# IPMC_MACP_-_1.net
KiCad netlist of a schematic drawn in Altium Designer
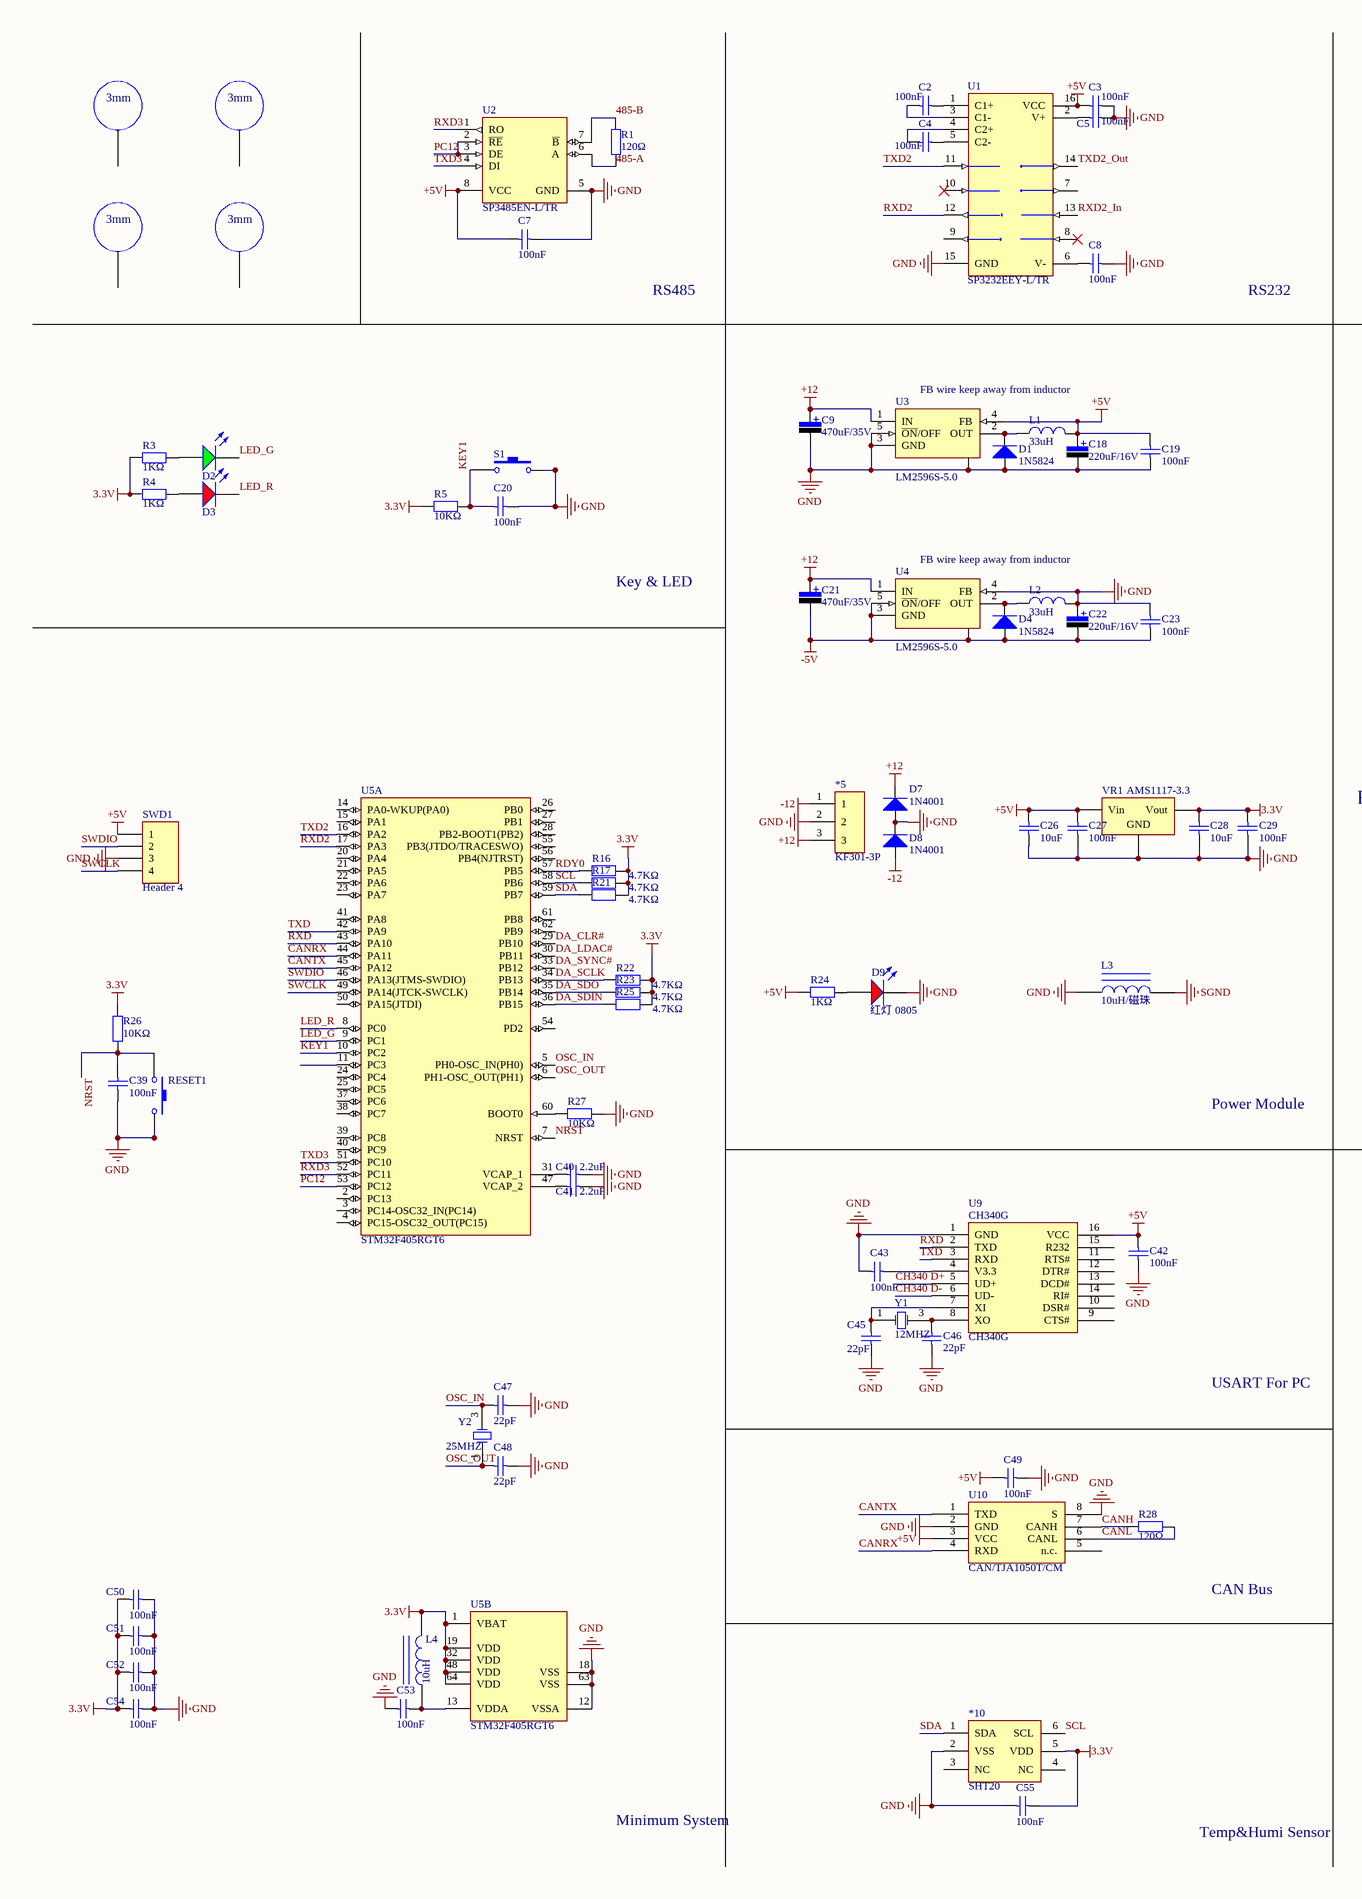
[diagram p0: IPMC_MACP - 完成1.SchDoc, left]
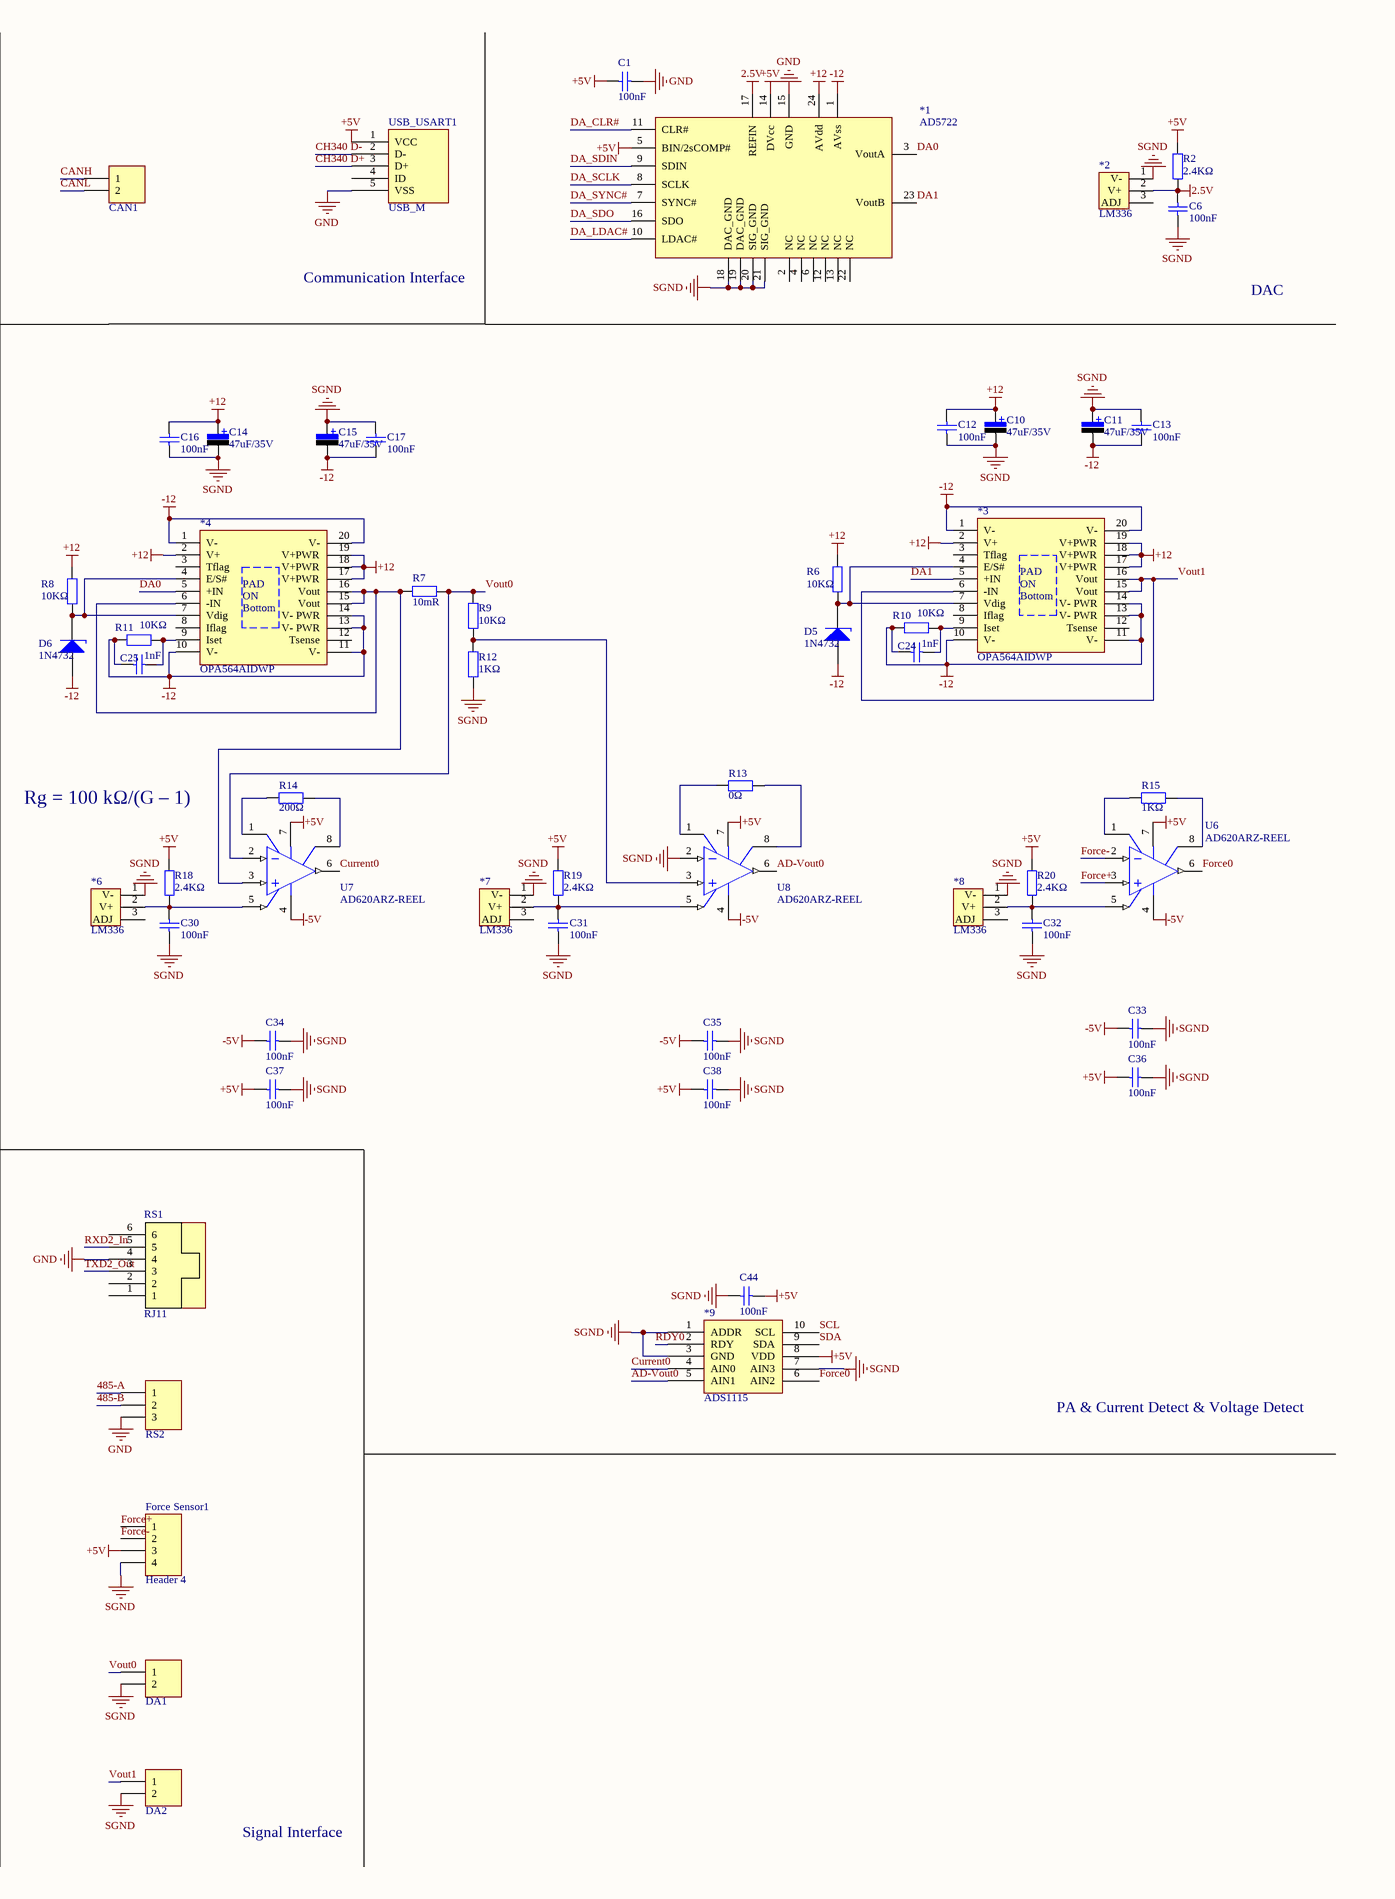
[diagram p1: IPMC_MACP - 完成1.SchDoc, right]

(export (version "E")
  (design (tool "Eeschema 10.0.6"))
  (components
    (comp (ref "*1")
      (value "AD5722")
      (footprint "TSSOP24P")
      (description "双极性DAC")
      (libsource (lib "fszhang") (part "AD5722"))
    )
    (comp (ref "*2")
      (value "LM336")
      (footprint "TO-92A")
      (description "基准电压芯片2.5/5V")
      (libsource (lib "fszhang") (part "LM336"))
    )
    (comp (ref "*3")
      (value "OPA564AIDWP")
      (footprint "HSOP20")
      (description "PAD on Bottom")
      (libsource (lib "fszhang") (part "OPA564AIDWP"))
    )
    (comp (ref "*4")
      (value "OPA564AIDWP")
      (footprint "HSOP20")
      (description "PAD on Bottom")
      (libsource (lib "fszhang") (part "OPA564AIDWP"))
    )
    (comp (ref "*5")
      (value "KF301-3P")
      (footprint "KF301-3P")
      (description "蓝色端子")
      (libsource (lib "fszhang") (part "KF301-3P"))
    )
    (comp (ref "*6")
      (value "LM336")
      (footprint "TO-92A")
      (description "基准电压芯片2.5/5V")
      (libsource (lib "fszhang") (part "LM336"))
    )
    (comp (ref "*7")
      (value "LM336")
      (footprint "TO-92A")
      (description "基准电压芯片2.5/5V")
      (libsource (lib "fszhang") (part "LM336"))
    )
    (comp (ref "*8")
      (value "LM336")
      (footprint "TO-92A")
      (description "基准电压芯片2.5/5V")
      (libsource (lib "fszhang") (part "LM336"))
    )
    (comp (ref "*9") (value "ADS1115") (footprint "MSOP-UN10_N") (libsource (lib "fszhang") (part "ADS1115")))
    (comp (ref "*10") (value "SHT20") (footprint "DFN6") (libsource (lib "fszhang") (part "SHT20")))
    (comp (ref "C1")
      (value "100nF")
      (footprint "0805_C")
      (description "贴片电容")
      (libsource (lib "Miscellaneous Devices LC") (part "0805 100nF(104) 10% 50V"))
    )
    (comp (ref "C2")
      (value "100nF")
      (footprint "0805_C")
      (description "贴片电容")
      (libsource (lib "Miscellaneous Devices LC") (part "0805 100nF(104) 10% 50V"))
    )
    (comp (ref "C3")
      (value "100nF")
      (footprint "0805_C")
      (description "贴片电容")
      (libsource (lib "Miscellaneous Devices LC") (part "0805 100nF(104) 10% 50V"))
    )
    (comp (ref "C4")
      (value "100nF")
      (footprint "0805_C")
      (description "贴片电容")
      (libsource (lib "Miscellaneous Devices LC") (part "0805 100nF(104) 10% 50V"))
    )
    (comp (ref "C5")
      (value "100nF")
      (footprint "0805_C")
      (description "贴片电容")
      (libsource (lib "Miscellaneous Devices LC") (part "0805 100nF(104) 10% 50V"))
    )
    (comp (ref "C6")
      (value "100nF")
      (footprint "0805_C")
      (description "贴片电容")
      (libsource (lib "Miscellaneous Devices LC") (part "0805 100nF(104) 10% 50V"))
    )
    (comp (ref "C7")
      (value "100nF")
      (footprint "0805_C")
      (description "贴片电容")
      (libsource (lib "Miscellaneous Devices LC") (part "0805 100nF(104) 10% 50V"))
    )
    (comp (ref "C8")
      (value "100nF")
      (footprint "0805_C")
      (description "贴片电容")
      (libsource (lib "Miscellaneous Devices LC") (part "0805 100nF(104) 10% 50V"))
    )
    (comp (ref "C9")
      (value "470uF/35V")
      (footprint "C-RB-S10")
      (description "极性电解电容")
      (fields (field (name "PUBLISHER") "Altium Limited"))
      (libsource (lib "fszhang") (part "Cap Pol"))
    )
    (comp (ref "C10")
      (value "47uF/35V")
      (footprint "C-RB-S6")
      (description "极性电解电容")
      (fields (field (name "PUBLISHER") "Altium Limited"))
      (libsource (lib "fszhang") (part "Cap Pol"))
    )
    (comp (ref "C11")
      (value "47uF/35V")
      (footprint "C-RB-S6")
      (description "极性电解电容")
      (fields (field (name "PUBLISHER") "Altium Limited"))
      (libsource (lib "fszhang") (part "Cap Pol"))
    )
    (comp (ref "C12")
      (value "100nF")
      (footprint "0805_C")
      (description "贴片电容")
      (libsource (lib "Miscellaneous Devices LC") (part "0805 100nF(104) 10% 50V"))
    )
    (comp (ref "C13")
      (value "100nF")
      (footprint "0805_C")
      (description "贴片电容")
      (libsource (lib "Miscellaneous Devices LC") (part "0805 100nF(104) 10% 50V"))
    )
    (comp (ref "C14")
      (value "47uF/35V")
      (footprint "C-RB-S6")
      (description "极性电解电容")
      (fields (field (name "PUBLISHER") "Altium Limited"))
      (libsource (lib "fszhang") (part "Cap Pol"))
    )
    (comp (ref "C15")
      (value "47uF/35V")
      (footprint "C-RB-S6")
      (description "极性电解电容")
      (fields (field (name "PUBLISHER") "Altium Limited"))
      (libsource (lib "fszhang") (part "Cap Pol"))
    )
    (comp (ref "C16")
      (value "100nF")
      (footprint "0805_C")
      (description "贴片电容")
      (libsource (lib "Miscellaneous Devices LC") (part "0805 100nF(104) 10% 50V"))
    )
    (comp (ref "C17")
      (value "100nF")
      (footprint "0805_C")
      (description "贴片电容")
      (libsource (lib "Miscellaneous Devices LC") (part "0805 100nF(104) 10% 50V"))
    )
    (comp (ref "C18")
      (value "220uF/16V")
      (footprint "C-RB-S6")
      (description "极性电解电容")
      (fields (field (name "PUBLISHER") "Altium Limited"))
      (libsource (lib "fszhang") (part "Cap Pol"))
    )
    (comp (ref "C19")
      (value "100nF")
      (footprint "0805_C")
      (description "贴片电容")
      (libsource (lib "Miscellaneous Devices LC") (part "0805 100nF(104) 10% 50V"))
    )
    (comp (ref "C20")
      (value "100nF")
      (footprint "0805_C")
      (description "贴片电容")
      (libsource (lib "Miscellaneous Devices LC") (part "0805 100nF(104) 10% 50V"))
    )
    (comp (ref "C21")
      (value "470uF/35V")
      (footprint "C-RB-S10")
      (description "极性电解电容")
      (fields (field (name "PUBLISHER") "Altium Limited"))
      (libsource (lib "fszhang") (part "Cap Pol"))
    )
    (comp (ref "C22")
      (value "220uF/16V")
      (footprint "C-RB-S6")
      (description "极性电解电容")
      (fields (field (name "PUBLISHER") "Altium Limited"))
      (libsource (lib "fszhang") (part "Cap Pol"))
    )
    (comp (ref "C23")
      (value "100nF")
      (footprint "0805_C")
      (description "贴片电容")
      (libsource (lib "Miscellaneous Devices LC") (part "0805 100nF(104) 10% 50V"))
    )
    (comp (ref "C24")
      (value "1nF")
      (footprint "0805_C")
      (description "贴片电容")
      (libsource (lib "Miscellaneous Devices LC") (part "0805 1nF (102) 10% 50V"))
    )
    (comp (ref "C25")
      (value "1nF")
      (footprint "0805_C")
      (description "贴片电容")
      (libsource (lib "Miscellaneous Devices LC") (part "0805 1nF (102) 10% 50V"))
    )
    (comp (ref "C26")
      (value "10uF")
      (footprint "0805_C")
      (description "贴片电容")
      (libsource (lib "Miscellaneous Devices LC") (part "0805 10uF (106) 10% 25V"))
    )
    (comp (ref "C27")
      (value "100nF")
      (footprint "0805_C")
      (description "贴片电容")
      (libsource (lib "Miscellaneous Devices LC") (part "0805 100nF(104) 10% 50V"))
    )
    (comp (ref "C28")
      (value "10uF")
      (footprint "0805_C")
      (description "贴片电容")
      (libsource (lib "Miscellaneous Devices LC") (part "0805 10uF (106) 10% 25V"))
    )
    (comp (ref "C29")
      (value "100nF")
      (footprint "0805_C")
      (description "贴片电容")
      (libsource (lib "Miscellaneous Devices LC") (part "0805 100nF(104) 10% 50V"))
    )
    (comp (ref "C30")
      (value "100nF")
      (footprint "0805_C")
      (description "贴片电容")
      (libsource (lib "Miscellaneous Devices LC") (part "0805 100nF(104) 10% 50V"))
    )
    (comp (ref "C31")
      (value "100nF")
      (footprint "0805_C")
      (description "贴片电容")
      (libsource (lib "Miscellaneous Devices LC") (part "0805 100nF(104) 10% 50V"))
    )
    (comp (ref "C32")
      (value "100nF")
      (footprint "0805_C")
      (description "贴片电容")
      (libsource (lib "Miscellaneous Devices LC") (part "0805 100nF(104) 10% 50V"))
    )
    (comp (ref "C33")
      (value "100nF")
      (footprint "0805_C")
      (description "贴片电容")
      (libsource (lib "Miscellaneous Devices LC") (part "0805 100nF(104) 10% 50V"))
    )
    (comp (ref "C34")
      (value "100nF")
      (footprint "0805_C")
      (description "贴片电容")
      (libsource (lib "Miscellaneous Devices LC") (part "0805 100nF(104) 10% 50V"))
    )
    (comp (ref "C35")
      (value "100nF")
      (footprint "0805_C")
      (description "贴片电容")
      (libsource (lib "Miscellaneous Devices LC") (part "0805 100nF(104) 10% 50V"))
    )
    (comp (ref "C36")
      (value "100nF")
      (footprint "0805_C")
      (description "贴片电容")
      (libsource (lib "Miscellaneous Devices LC") (part "0805 100nF(104) 10% 50V"))
    )
    (comp (ref "C37")
      (value "100nF")
      (footprint "0805_C")
      (description "贴片电容")
      (libsource (lib "Miscellaneous Devices LC") (part "0805 100nF(104) 10% 50V"))
    )
    (comp (ref "C38")
      (value "100nF")
      (footprint "0805_C")
      (description "贴片电容")
      (libsource (lib "Miscellaneous Devices LC") (part "0805 100nF(104) 10% 50V"))
    )
    (comp (ref "C39")
      (value "100nF")
      (footprint "0805_C")
      (description "贴片电容")
      (libsource (lib "Miscellaneous Devices LC") (part "0805 100nF(104) 10% 50V"))
    )
    (comp (ref "C40")
      (value "2.2uF")
      (footprint "0805_C")
      (description "贴片电容")
      (libsource (lib "Miscellaneous Devices LC") (part "0805 2.2uF (225) 20% 50V"))
    )
    (comp (ref "C41")
      (value "2.2uF")
      (footprint "0805_C")
      (description "贴片电容")
      (libsource (lib "Miscellaneous Devices LC") (part "0805 2.2uF (225) 20% 50V"))
    )
    (comp (ref "C42")
      (value "100nF")
      (footprint "0805_C")
      (description "贴片电容")
      (libsource (lib "Miscellaneous Devices LC") (part "0805 100nF(104) 10% 50V"))
    )
    (comp (ref "C43")
      (value "100nF")
      (footprint "0805_C")
      (description "贴片电容")
      (libsource (lib "Miscellaneous Devices LC") (part "0805 100nF(104) 10% 50V"))
    )
    (comp (ref "C44")
      (value "100nF")
      (footprint "0805_C")
      (description "贴片电容")
      (libsource (lib "Miscellaneous Devices LC") (part "0805 100nF(104) 10% 50V"))
    )
    (comp (ref "C45")
      (value "22pF")
      (footprint "0805_C")
      (description "贴片电容")
      (libsource (lib "Miscellaneous Devices LC") (part "0805 22pF (220) 5% 50V"))
    )
    (comp (ref "C46")
      (value "22pF")
      (footprint "0805_C")
      (description "贴片电容")
      (libsource (lib "Miscellaneous Devices LC") (part "0805 22pF (220) 5% 50V"))
    )
    (comp (ref "C47")
      (value "22pF")
      (footprint "0805_C")
      (description "贴片电容")
      (libsource (lib "Miscellaneous Devices LC") (part "0805 22pF (220) 5% 50V"))
    )
    (comp (ref "C48")
      (value "22pF")
      (footprint "0805_C")
      (description "贴片电容")
      (libsource (lib "Miscellaneous Devices LC") (part "0805 22pF (220) 5% 50V"))
    )
    (comp (ref "C49")
      (value "100nF")
      (footprint "0805_C")
      (description "贴片电容")
      (libsource (lib "Miscellaneous Devices LC") (part "0805 100nF(104) 10% 50V"))
    )
    (comp (ref "C50")
      (value "100nF")
      (footprint "0805_C")
      (description "贴片电容")
      (libsource (lib "Miscellaneous Devices LC") (part "0805 100nF(104) 10% 50V"))
    )
    (comp (ref "C51")
      (value "100nF")
      (footprint "0805_C")
      (description "贴片电容")
      (libsource (lib "Miscellaneous Devices LC") (part "0805 100nF(104) 10% 50V"))
    )
    (comp (ref "C52")
      (value "100nF")
      (footprint "0805_C")
      (description "贴片电容")
      (libsource (lib "Miscellaneous Devices LC") (part "0805 100nF(104) 10% 50V"))
    )
    (comp (ref "C53")
      (value "100nF")
      (footprint "0805_C")
      (description "贴片电容")
      (libsource (lib "Miscellaneous Devices LC") (part "0805 100nF(104) 10% 50V"))
    )
    (comp (ref "C54")
      (value "100nF")
      (footprint "0805_C")
      (description "贴片电容")
      (libsource (lib "Miscellaneous Devices LC") (part "0805 100nF(104) 10% 50V"))
    )
    (comp (ref "C55")
      (value "100nF")
      (footprint "0805_C")
      (description "贴片电容")
      (libsource (lib "Miscellaneous Devices LC") (part "0805 100nF(104) 10% 50V"))
    )
    (comp (ref "CAN1")
      (value "Header 2")
      (footprint "HDR2X1_B1")
      (description "接插件")
      (fields (field (name "PUBLISHER") "Altium Limited"))
      (libsource (lib "fszhang") (part "Header 2"))
    )
    (comp (ref "D1")
      (value "1N5824")
      (footprint "DIODE-SMA")
      (description "二极管")
      (fields (field (name "PUBLISHER") "Altium Limited"))
      (libsource (lib "fszhang") (part "Diode"))
    )
    (comp (ref "D2")
      (value "翠绿 0805")
      (footprint "0805_LED_S1")
      (description "发光二极管")
      (libsource (lib "Miscellaneous Devices LC") (part "0805 翠绿"))
    )
    (comp (ref "D3")
      (value "红灯 0805")
      (footprint "0805_LED_S1")
      (description "发光二极管")
      (libsource (lib "Miscellaneous Devices LC") (part "0805 红灯"))
    )
    (comp (ref "D4")
      (value "1N5824")
      (footprint "DIODE-SMA")
      (description "二极管")
      (fields (field (name "PUBLISHER") "Altium Limited"))
      (libsource (lib "fszhang") (part "Diode"))
    )
    (comp (ref "D5")
      (value "1N4732")
      (footprint "DIODE-1206")
      (description "稳压二极管")
      (fields (field (name "PUBLISHER") "Altium Limited"))
      (libsource (lib "fszhang") (part "Diode-Z"))
    )
    (comp (ref "D6")
      (value "1N4732")
      (footprint "DIODE-1206")
      (description "稳压二极管")
      (fields (field (name "PUBLISHER") "Altium Limited"))
      (libsource (lib "fszhang") (part "Diode-Z"))
    )
    (comp (ref "D7")
      (value "1N4001")
      (footprint "DIODE-SMA")
      (description "二极管")
      (fields (field (name "PUBLISHER") "Altium Limited"))
      (libsource (lib "fszhang") (part "Diode"))
    )
    (comp (ref "D8")
      (value "1N4001")
      (footprint "DIODE-SMA")
      (description "二极管")
      (fields (field (name "PUBLISHER") "Altium Limited"))
      (libsource (lib "fszhang") (part "Diode"))
    )
    (comp (ref "D9")
      (value "红灯 0805")
      (footprint "0805_LED_S1")
      (description "发光二极管")
      (libsource (lib "Miscellaneous Devices LC") (part "0805 红灯"))
    )
    (comp (ref "DA1")
      (value "Header 2")
      (footprint "HDR2X1_B1")
      (description "接插件")
      (fields (field (name "PUBLISHER") "Altium Limited"))
      (libsource (lib "fszhang") (part "Header 2"))
    )
    (comp (ref "DA2")
      (value "Header 2")
      (footprint "HDR2X1_B1")
      (description "接插件")
      (fields (field (name "PUBLISHER") "Altium Limited"))
      (libsource (lib "fszhang") (part "Header 2"))
    )
    (comp (ref "Force Sensor1")
      (value "Header 4")
      (footprint "fszhang:HDR4X1_B1")
      (description "Header, 4-Pin")
      (fields (field (name "PUBLISHER") "Altium Limited"))
      (libsource (lib "Miscellaneous Connectors") (part "Header 4"))
    )
    (comp (ref "L1")
      (value "33uH")
      (footprint "L-SMD-12")
      (description "电感")
      (fields (field (name "PUBLISHER") "Altium Limited"))
      (libsource (lib "fszhang") (part "Inductor"))
    )
    (comp (ref "L2")
      (value "33uH")
      (footprint "L-SMD-12")
      (description "电感")
      (fields (field (name "PUBLISHER") "Altium Limited"))
      (libsource (lib "fszhang") (part "Inductor"))
    )
    (comp (ref "L3")
      (value "10uH/磁珠")
      (footprint "0805_L")
      (description "贴片电感")
      (libsource (lib "Miscellaneous Devices LC") (part "0805 10uH 10%"))
    )
    (comp (ref "L4")
      (value "10uH")
      (footprint "0805_L")
      (description "贴片电感")
      (libsource (lib "Miscellaneous Devices LC") (part "0805 10uH 10%"))
    )
    (comp (ref "R1")
      (value "120Ω")
      (footprint "0805_R")
      (description "贴片电阻")
      (libsource (lib "Miscellaneous Devices LC") (part "0805 120Ω (1200) 1%"))
    )
    (comp (ref "R2")
      (value "2.4KΩ")
      (footprint "0805_R")
      (description "贴片电阻")
      (libsource (lib "Miscellaneous Devices LC") (part "0805 2.4KΩ (2401) 1%"))
    )
    (comp (ref "R3")
      (value "1KΩ")
      (footprint "0805_R")
      (description "贴片电阻")
      (libsource (lib "Miscellaneous Devices LC") (part "0805 1KΩ (1001) 1%"))
    )
    (comp (ref "R4")
      (value "1KΩ")
      (footprint "0805_R")
      (description "贴片电阻")
      (libsource (lib "Miscellaneous Devices LC") (part "0805 1KΩ (1001) 1%"))
    )
    (comp (ref "R5")
      (value "10KΩ")
      (footprint "0805_R")
      (description "贴片电阻")
      (libsource (lib "") (part "0805 10KΩ (1002) 1%_2"))
    )
    (comp (ref "R6")
      (value "10KΩ")
      (footprint "0805_R")
      (description "贴片电阻")
      (libsource (lib "") (part "0805 10KΩ (1002) 1%_3"))
    )
    (comp (ref "R7")
      (value "10mR")
      (footprint "2512")
      (description "贴片电阻")
      (fields (field (name "PUBLISHER") "Altium Limited"))
      (libsource (lib "fszhang") (part "Res1"))
    )
    (comp (ref "R8")
      (value "10KΩ")
      (footprint "0805_R")
      (description "贴片电阻")
      (libsource (lib "") (part "0805 10KΩ (1002) 1%_3"))
    )
    (comp (ref "R9")
      (value "10KΩ")
      (footprint "0805_R")
      (description "贴片电阻")
      (libsource (lib "Miscellaneous Devices LC") (part "0805 20KΩ (2002) 1%"))
    )
    (comp (ref "R10")
      (value "10KΩ")
      (footprint "0805_R")
      (description "贴片电阻")
      (libsource (lib "") (part "0805 10KΩ (1002) 1%_2"))
    )
    (comp (ref "R11")
      (value "10KΩ")
      (footprint "0805_R")
      (description "贴片电阻")
      (libsource (lib "") (part "0805 10KΩ (1002) 1%_2"))
    )
    (comp (ref "R12")
      (value "1KΩ")
      (footprint "0805_R")
      (description "贴片电阻")
      (libsource (lib "Miscellaneous Devices LC") (part "0805 20KΩ (2002) 1%"))
    )
    (comp (ref "R13")
      (value "0Ω")
      (footprint "0805_R")
      (description "贴片电阻")
      (libsource (lib "Miscellaneous Devices LC") (part "0805 0Ω (0R0) 1%"))
    )
    (comp (ref "R14")
      (value "200Ω")
      (footprint "0805_R")
      (description "贴片电阻")
      (libsource (lib "Miscellaneous Devices LC") (part "0805 200Ω (2000) 1%"))
    )
    (comp (ref "R15")
      (value "1KΩ")
      (footprint "0805_R")
      (description "贴片电阻")
      (libsource (lib "Miscellaneous Devices LC") (part "0805 1KΩ (1001) 1%"))
    )
    (comp (ref "R16")
      (value "4.7KΩ")
      (footprint "0805_R")
      (description "贴片电阻")
      (libsource (lib "Miscellaneous Devices LC") (part "0805 4.7KΩ (4701) 1%"))
    )
    (comp (ref "R17")
      (value "4.7KΩ")
      (footprint "0805_R")
      (description "贴片电阻")
      (libsource (lib "Miscellaneous Devices LC") (part "0805 4.7KΩ (4701) 1%"))
    )
    (comp (ref "R18")
      (value "2.4KΩ")
      (footprint "0805_R")
      (description "贴片电阻")
      (libsource (lib "Miscellaneous Devices LC") (part "0805 2.4KΩ (2401) 1%"))
    )
    (comp (ref "R19")
      (value "2.4KΩ")
      (footprint "0805_R")
      (description "贴片电阻")
      (libsource (lib "Miscellaneous Devices LC") (part "0805 2.4KΩ (2401) 1%"))
    )
    (comp (ref "R20")
      (value "2.4KΩ")
      (footprint "0805_R")
      (description "贴片电阻")
      (libsource (lib "Miscellaneous Devices LC") (part "0805 2.4KΩ (2401) 1%"))
    )
    (comp (ref "R21")
      (value "4.7KΩ")
      (footprint "0805_R")
      (description "贴片电阻")
      (libsource (lib "Miscellaneous Devices LC") (part "0805 4.7KΩ (4701) 1%"))
    )
    (comp (ref "R22")
      (value "4.7KΩ")
      (footprint "0805_R")
      (description "贴片电阻")
      (libsource (lib "Miscellaneous Devices LC") (part "0805 4.7KΩ (4701) 1%"))
    )
    (comp (ref "R23")
      (value "4.7KΩ")
      (footprint "0805_R")
      (description "贴片电阻")
      (libsource (lib "Miscellaneous Devices LC") (part "0805 4.7KΩ (4701) 1%"))
    )
    (comp (ref "R24")
      (value "1KΩ")
      (footprint "0805_R")
      (description "贴片电阻")
      (libsource (lib "Miscellaneous Devices LC") (part "0805 1KΩ (1001) 1%"))
    )
    (comp (ref "R25")
      (value "4.7KΩ")
      (footprint "0805_R")
      (description "贴片电阻")
      (libsource (lib "Miscellaneous Devices LC") (part "0805 4.7KΩ (4701) 1%"))
    )
    (comp (ref "R26")
      (value "10KΩ")
      (footprint "0805_R")
      (description "贴片电阻")
      (libsource (lib "Miscellaneous Devices LC") (part "0805 10KΩ (1002) 1%"))
    )
    (comp (ref "R27")
      (value "10KΩ")
      (footprint "0805_R")
      (description "贴片电阻")
      (libsource (lib "") (part "0805 10KΩ (1002) 1%_1"))
    )
    (comp (ref "R28")
      (value "120Ω")
      (footprint "0805_R")
      (description "贴片电阻")
      (libsource (lib "") (part "0805 120Ω (1200) 1%_1"))
    )
    (comp (ref "RESET1")
      (value "SW-PB")
      (footprint "SW_PB2_A1")
      (description "微动开关")
      (fields (field (name "PUBLISHER") "Altium Limited"))
      (libsource (lib "fszhang") (part "SW-PB"))
    )
    (comp (ref "RS1") (value "RJ11") (footprint "RJ6-RJ11") (libsource (lib "fszhang") (part "RJ11")))
    (comp (ref "RS2")
      (value "Header 3")
      (footprint "HDR3X1_B1")
      (description "接插件")
      (fields (field (name "PUBLISHER") "Altium Limited"))
      (libsource (lib "fszhang") (part "Header 3"))
    )
    (comp (ref "S1")
      (value "SW-PB")
      (footprint "SW_PB2_A1")
      (description "微动开关")
      (fields (field (name "PUBLISHER") "Altium Limited"))
      (libsource (lib "fszhang") (part "SW-PB"))
    )
    (comp (ref "SWD1")
      (value "Header 4")
      (footprint "HDR1X4")
      (description "Header, 4-Pin")
      (fields (field (name "PUBLISHER") "Altium Limited"))
      (libsource (lib "Miscellaneous Connectors") (part "Header 4"))
    )
    (comp (ref "T1") (value "M3铜柱螺丝孔") (footprint "螺丝孔-3mm") (libsource (lib "fszhang") (part "M3铜柱螺丝孔")))
    (comp (ref "T2") (value "M3铜柱螺丝孔") (footprint "螺丝孔-3mm") (libsource (lib "fszhang") (part "M3铜柱螺丝孔")))
    (comp (ref "T3") (value "M3铜柱螺丝孔") (footprint "螺丝孔-3mm") (libsource (lib "fszhang") (part "M3铜柱螺丝孔")))
    (comp (ref "T4") (value "M3铜柱螺丝孔") (footprint "螺丝孔-3mm") (libsource (lib "fszhang") (part "M3铜柱螺丝孔")))
    (comp (ref "U1")
      (value "SP3232EEY-L/TR")
      (footprint "TSSOP-16")
      (description "RS232")
      (libsource (lib "Miscellaneous Devices LC") (part "SP3232EEY-L/TR"))
    )
    (comp (ref "U2")
      (value "SP3485EN-L/TR")
      (footprint "SOIC-8_150mil")
      (description "RS-485/RS-422")
      (libsource (lib "Miscellaneous Devices LC") (part "SP3485EN-L/TR"))
    )
    (comp (ref "U3")
      (value "LM2596S-5.0")
      (footprint "TO-263-5")
      (description "5V稳压芯片")
      (fields (field (name "PUBLISHER") "Altium Limited"))
      (libsource (lib "fszhang") (part "LM2596S-5.0"))
    )
    (comp (ref "U4")
      (value "LM2596S-5.0")
      (footprint "TO-263-5")
      (description "5V稳压芯片")
      (fields (field (name "PUBLISHER") "Altium Limited"))
      (libsource (lib "fszhang") (part "LM2596S-5.0"))
    )
    (comp (ref "U5")
      (value "STM32F405RGT6")
      (footprint "STM-LQFP64_L")
      (fields (field (name "MANUFACTURER") "STMicroelectronics"))
      (libsource (lib "STMicroelectronics STM32 F4") (part "STM32F405RGT6"))
    )
    (comp (ref "U6")
      (value "AD620ARZ-REEL")
      (footprint "SOIC-8_150mil")
      (description "仪放")
      (libsource (lib "Miscellaneous Devices LC") (part "AD620ARZ-REEL"))
    )
    (comp (ref "U7")
      (value "AD620ARZ-REEL")
      (footprint "SOIC-8_150mil")
      (description "仪放")
      (libsource (lib "Miscellaneous Devices LC") (part "AD620ARZ-REEL"))
    )
    (comp (ref "U8")
      (value "AD620ARZ-REEL")
      (footprint "SOIC-8_150mil")
      (description "仪放")
      (libsource (lib "Miscellaneous Devices LC") (part "AD620ARZ-REEL"))
    )
    (comp (ref "U9")
      (value "CH340G")
      (footprint "SOIC-16_150mil")
      (description "USB")
      (libsource (lib "Miscellaneous Devices LC") (part "CH340G"))
    )
    (comp (ref "U10")
      (value "CAN/TJA1050T/CM")
      (footprint "SOIC-8_150mil")
      (description "CAN")
      (libsource (lib "Miscellaneous Devices LC") (part "CAN/TJA1050T/CM"))
    )
    (comp (ref "USB_USART1")
      (value "USB_M")
      (footprint "USB_MICRO")
      (description "MicroUSB接口")
      (libsource (lib "fszhang") (part "USB_M"))
    )
    (comp (ref "VR1")
      (value "AMS1117-3.3")
      (footprint "SOT-223")
      (description "低压差线性稳压(LDO)")
      (libsource (lib "Miscellaneous Devices LC") (part "SOT-223 AMS1117-3.3"))
    )
    (comp (ref "Y1")
      (value "12MHZ")
      (footprint "SMD-3225_4P")
      (description "贴片晶振")
      (libsource (lib "Miscellaneous Devices LC") (part "SMD-3225_4P  12MHZ 20PF 10PPM"))
    )
    (comp (ref "Y2")
      (value "25MHZ")
      (footprint "SMD-3225_4P")
      (description "贴片晶振")
      (libsource (lib "Miscellaneous Devices LC") (part "SMD-3225_4P  25MHZ 12PF 10PPM"))
    )
  )
  (nets
    (net (code "1") (name "+5V") (class "Default")
      (node (ref "*1") (pin "14") (pinfunction "DVcc_14") (pintype "passive"))
      (node (ref "*1") (pin "5") (pinfunction "BIN/2sCOMP#_5") (pintype "passive"))
      (node (ref "*9") (pin "8") (pinfunction "VDD_8") (pintype "passive"))
      (node (ref "C1") (pin "2") (pinfunction "2_2") (pintype "passive"))
      (node (ref "C18") (pin "1") (pinfunction "1_1") (pintype "passive"))
      (node (ref "C19") (pin "2") (pinfunction "2_2") (pintype "passive"))
      (node (ref "C26") (pin "2") (pinfunction "2_2") (pintype "passive"))
      (node (ref "C27") (pin "2") (pinfunction "2_2") (pintype "passive"))
      (node (ref "C3") (pin "1") (pinfunction "1_1") (pintype "passive"))
      (node (ref "C36") (pin "2") (pinfunction "2_2") (pintype "passive"))
      (node (ref "C37") (pin "2") (pinfunction "2_2") (pintype "passive"))
      (node (ref "C38") (pin "2") (pinfunction "2_2") (pintype "passive"))
      (node (ref "C42") (pin "2") (pinfunction "2_2") (pintype "passive"))
      (node (ref "C44") (pin "1") (pinfunction "1_1") (pintype "passive"))
      (node (ref "C49") (pin "2") (pinfunction "2_2") (pintype "passive"))
      (node (ref "C7") (pin "2") (pinfunction "2_2") (pintype "passive"))
      (node (ref "Force Sensor1") (pin "3") (pinfunction "3_3") (pintype "passive"))
      (node (ref "L1") (pin "2") (pinfunction "2_2") (pintype "passive"))
      (node (ref "R18") (pin "2") (pinfunction "2_2") (pintype "passive"))
      (node (ref "R19") (pin "2") (pinfunction "2_2") (pintype "passive"))
      (node (ref "R2") (pin "2") (pinfunction "2_2") (pintype "passive"))
      (node (ref "R20") (pin "2") (pinfunction "2_2") (pintype "passive"))
      (node (ref "R24") (pin "1") (pinfunction "1_1") (pintype "passive"))
      (node (ref "SWD1") (pin "1") (pinfunction "1_1") (pintype "passive"))
      (node (ref "U1") (pin "16") (pinfunction "VCC_16") (pintype "power_in"))
      (node (ref "U10") (pin "3") (pinfunction "VCC_3") (pintype "passive"))
      (node (ref "U2") (pin "8") (pinfunction "VCC_8") (pintype "power_in"))
      (node (ref "U3") (pin "4") (pinfunction "FB_4") (pintype "input"))
      (node (ref "U6") (pin "7") (pinfunction "V+_7") (pintype "power_in"))
      (node (ref "U7") (pin "7") (pinfunction "V+_7") (pintype "power_in"))
      (node (ref "U8") (pin "7") (pinfunction "V+_7") (pintype "power_in"))
      (node (ref "U9") (pin "16") (pinfunction "VCC_16") (pintype "passive"))
      (node (ref "USB_USART1") (pin "1") (pinfunction "VCC_1") (pintype "passive"))
      (node (ref "VR1") (pin "3") (pinfunction "Vin_3") (pintype "passive"))
    )
    (net (code "2") (name "+12") (class "Default")
      (node (ref "*1") (pin "24") (pinfunction "AVdd_24") (pintype "passive"))
      (node (ref "*3") (pin "17") (pinfunction "V+PWR_17") (pintype "passive"))
      (node (ref "*3") (pin "18") (pinfunction "V+PWR_18") (pintype "passive"))
      (node (ref "*3") (pin "19") (pinfunction "V+PWR_19") (pintype "passive"))
      (node (ref "*3") (pin "2") (pinfunction "V+_2") (pintype "passive"))
      (node (ref "*4") (pin "17") (pinfunction "V+PWR_17") (pintype "passive"))
      (node (ref "*4") (pin "18") (pinfunction "V+PWR_18") (pintype "passive"))
      (node (ref "*4") (pin "19") (pinfunction "V+PWR_19") (pintype "passive"))
      (node (ref "*4") (pin "2") (pinfunction "V+_2") (pintype "passive"))
      (node (ref "*5") (pin "3") (pinfunction "3_3") (pintype "passive"))
      (node (ref "C10") (pin "1") (pinfunction "1_1") (pintype "passive"))
      (node (ref "C12") (pin "2") (pinfunction "2_2") (pintype "passive"))
      (node (ref "C14") (pin "1") (pinfunction "1_1") (pintype "passive"))
      (node (ref "C16") (pin "2") (pinfunction "2_2") (pintype "passive"))
      (node (ref "C21") (pin "1") (pinfunction "1_1") (pintype "passive"))
      (node (ref "C9") (pin "1") (pinfunction "1_1") (pintype "passive"))
      (node (ref "D7") (pin "2") (pinfunction "K_2") (pintype "passive"))
      (node (ref "R6") (pin "2") (pinfunction "2_2") (pintype "passive"))
      (node (ref "R8") (pin "2") (pinfunction "2_2") (pintype "passive"))
      (node (ref "U3") (pin "1") (pinfunction "IN_1") (pintype "power_in"))
      (node (ref "U4") (pin "1") (pinfunction "IN_1") (pintype "power_in"))
    )
    (net (code "3") (name "-5V") (class "Default")
      (node (ref "C21") (pin "2") (pinfunction "2_2") (pintype "passive"))
      (node (ref "C22") (pin "2") (pinfunction "2_2") (pintype "passive"))
      (node (ref "C23") (pin "1") (pinfunction "1_1") (pintype "passive"))
      (node (ref "C33") (pin "2") (pinfunction "2_2") (pintype "passive"))
      (node (ref "C34") (pin "2") (pinfunction "2_2") (pintype "passive"))
      (node (ref "C35") (pin "2") (pinfunction "2_2") (pintype "passive"))
      (node (ref "D4") (pin "1") (pinfunction "A_1") (pintype "passive"))
      (node (ref "U4") (pin "3") (pinfunction "GND_3") (pintype "power_in"))
      (node (ref "U4") (pin "5") (pinfunction "~{ON}/OFF_5") (pintype "input"))
      (node (ref "U4") (pin "6") (pinfunction "6_6") (pintype "power_in"))
      (node (ref "U6") (pin "4") (pinfunction "V-_4") (pintype "power_in"))
      (node (ref "U7") (pin "4") (pinfunction "V-_4") (pintype "power_in"))
      (node (ref "U8") (pin "4") (pinfunction "V-_4") (pintype "power_in"))
    )
    (net (code "4") (name "-12") (class "Default")
      (node (ref "*1") (pin "1") (pinfunction "AVss_1") (pintype "passive"))
      (node (ref "*3") (pin "1") (pinfunction "V-_1") (pintype "passive"))
      (node (ref "*3") (pin "10") (pinfunction "V-_10") (pintype "passive"))
      (node (ref "*3") (pin "11") (pinfunction "V-_11") (pintype "passive"))
      (node (ref "*3") (pin "13") (pinfunction "V-_PWR_13") (pintype "passive"))
      (node (ref "*3") (pin "14") (pinfunction "V-_PWR_14") (pintype "passive"))
      (node (ref "*3") (pin "20") (pinfunction "V-_20") (pintype "passive"))
      (node (ref "*4") (pin "1") (pinfunction "V-_1") (pintype "passive"))
      (node (ref "*4") (pin "10") (pinfunction "V-_10") (pintype "passive"))
      (node (ref "*4") (pin "11") (pinfunction "V-_11") (pintype "passive"))
      (node (ref "*4") (pin "13") (pinfunction "V-_PWR_13") (pintype "passive"))
      (node (ref "*4") (pin "14") (pinfunction "V-_PWR_14") (pintype "passive"))
      (node (ref "*4") (pin "20") (pinfunction "V-_20") (pintype "passive"))
      (node (ref "*5") (pin "1") (pinfunction "1_1") (pintype "passive"))
      (node (ref "C11") (pin "2") (pinfunction "2_2") (pintype "passive"))
      (node (ref "C13") (pin "2") (pinfunction "2_2") (pintype "passive"))
      (node (ref "C15") (pin "2") (pinfunction "2_2") (pintype "passive"))
      (node (ref "C17") (pin "2") (pinfunction "2_2") (pintype "passive"))
      (node (ref "C24") (pin "1") (pinfunction "1_1") (pintype "passive"))
      (node (ref "C25") (pin "1") (pinfunction "1_1") (pintype "passive"))
      (node (ref "D5") (pin "1") (pinfunction "A_1") (pintype "passive"))
      (node (ref "D6") (pin "1") (pinfunction "A_1") (pintype "passive"))
      (node (ref "D8") (pin "1") (pinfunction "A_1") (pintype "passive"))
      (node (ref "R10") (pin "1") (pinfunction "1_1") (pintype "passive"))
      (node (ref "R11") (pin "1") (pinfunction "1_1") (pintype "passive"))
    )
    (net (code "5") (name "/485-A") (class "Default")
      (node (ref "R1") (pin "1") (pinfunction "1_1") (pintype "passive"))
      (node (ref "RS2") (pin "1") (pinfunction "1_1") (pintype "passive"))
      (node (ref "U2") (pin "6") (pinfunction "A_6") (pintype "bidirectional"))
    )
    (net (code "6") (name "/485-B") (class "Default")
      (node (ref "R1") (pin "2") (pinfunction "2_2") (pintype "passive"))
      (node (ref "RS2") (pin "2") (pinfunction "2_2") (pintype "passive"))
      (node (ref "U2") (pin "7") (pinfunction "~{B}_7") (pintype "bidirectional"))
    )
    (net (code "7") (name "/AD-Vout0") (class "Default")
      (node (ref "*9") (pin "5") (pinfunction "AIN1_5") (pintype "passive"))
      (node (ref "U8") (pin "6") (pinfunction "OUT_6") (pintype "output"))
    )
    (net (code "8") (name "/CANH") (class "Default")
      (node (ref "CAN1") (pin "1") (pinfunction "1_1") (pintype "passive"))
      (node (ref "R28") (pin "1") (pinfunction "1_1") (pintype "passive"))
      (node (ref "U10") (pin "7") (pinfunction "CANH_7") (pintype "passive"))
    )
    (net (code "9") (name "/CANL") (class "Default")
      (node (ref "CAN1") (pin "2") (pinfunction "2_2") (pintype "passive"))
      (node (ref "R28") (pin "2") (pinfunction "2_2") (pintype "passive"))
      (node (ref "U10") (pin "6") (pinfunction "CANL_6") (pintype "passive"))
    )
    (net (code "10") (name "/CANRX") (class "Default")
      (node (ref "U10") (pin "4") (pinfunction "RXD_4") (pintype "passive"))
      (node (ref "U5") (pin "44") (pinfunction "PA11_44") (pintype "bidirectional"))
    )
    (net (code "11") (name "/CANTX") (class "Default")
      (node (ref "U10") (pin "1") (pinfunction "TXD_1") (pintype "passive"))
      (node (ref "U5") (pin "45") (pinfunction "PA12_45") (pintype "bidirectional"))
    )
    (net (code "12") (name "/CH340 D+") (class "Default")
      (node (ref "U9") (pin "5") (pinfunction "UD+_5") (pintype "passive"))
      (node (ref "USB_USART1") (pin "3") (pinfunction "D+_3") (pintype "passive"))
    )
    (net (code "13") (name "/CH340 D-") (class "Default")
      (node (ref "U9") (pin "6") (pinfunction "UD-_6") (pintype "passive"))
      (node (ref "USB_USART1") (pin "2") (pinfunction "D-_2") (pintype "passive"))
    )
    (net (code "14") (name "/Current0") (class "Default")
      (node (ref "*9") (pin "4") (pinfunction "AIN0_4") (pintype "passive"))
      (node (ref "U7") (pin "6") (pinfunction "OUT_6") (pintype "output"))
    )
    (net (code "15") (name "/DA0") (class "Default")
      (node (ref "*1") (pin "3") (pinfunction "VoutA_3") (pintype "passive"))
      (node (ref "*4") (pin "5") (pinfunction "+IN_5") (pintype "passive"))
    )
    (net (code "16") (name "/DA1") (class "Default")
      (node (ref "*1") (pin "23") (pinfunction "VoutB_23") (pintype "passive"))
      (node (ref "*3") (pin "5") (pinfunction "+IN_5") (pintype "passive"))
    )
    (net (code "17") (name "/DA_CLR#") (class "Default")
      (node (ref "*1") (pin "11") (pinfunction "CLR#_11") (pintype "passive"))
      (node (ref "U5") (pin "29") (pinfunction "PB10_29") (pintype "bidirectional"))
    )
    (net (code "18") (name "/DA_LDAC#") (class "Default")
      (node (ref "*1") (pin "10") (pinfunction "LDAC#_10") (pintype "passive"))
      (node (ref "U5") (pin "30") (pinfunction "PB11_30") (pintype "bidirectional"))
    )
    (net (code "19") (name "/DA_SCLK") (class "Default")
      (node (ref "*1") (pin "8") (pinfunction "SCLK_8") (pintype "passive"))
      (node (ref "R22") (pin "1") (pinfunction "1_1") (pintype "passive"))
      (node (ref "U5") (pin "34") (pinfunction "PB13_34") (pintype "bidirectional"))
    )
    (net (code "20") (name "/DA_SDIN") (class "Default")
      (node (ref "*1") (pin "9") (pinfunction "SDIN_9") (pintype "passive"))
      (node (ref "R25") (pin "1") (pinfunction "1_1") (pintype "passive"))
      (node (ref "U5") (pin "36") (pinfunction "PB15_36") (pintype "bidirectional"))
    )
    (net (code "21") (name "/DA_SDO") (class "Default")
      (node (ref "*1") (pin "16") (pinfunction "SDO_16") (pintype "passive"))
      (node (ref "R23") (pin "1") (pinfunction "1_1") (pintype "passive"))
      (node (ref "U5") (pin "35") (pinfunction "PB14_35") (pintype "bidirectional"))
    )
    (net (code "22") (name "/DA_SYNC#") (class "Default")
      (node (ref "*1") (pin "7") (pinfunction "SYNC#_7") (pintype "passive"))
      (node (ref "U5") (pin "33") (pinfunction "PB12_33") (pintype "bidirectional"))
    )
    (net (code "23") (name "/Force+") (class "Default")
      (node (ref "Force Sensor1") (pin "1") (pinfunction "1_1") (pintype "passive"))
      (node (ref "U6") (pin "3") (pinfunction "+IN_3") (pintype "input"))
    )
    (net (code "24") (name "/Force-") (class "Default")
      (node (ref "Force Sensor1") (pin "2") (pinfunction "2_2") (pintype "passive"))
      (node (ref "U6") (pin "2") (pinfunction "-IN_2") (pintype "input"))
    )
    (net (code "25") (name "/Force0") (class "Default")
      (node (ref "*9") (pin "6") (pinfunction "AIN2_6") (pintype "passive"))
      (node (ref "U6") (pin "6") (pinfunction "OUT_6") (pintype "output"))
    )
    (net (code "26") (name "/KEY1") (class "Default")
      (node (ref "C20") (pin "1") (pinfunction "1_1") (pintype "passive"))
      (node (ref "R5") (pin "2") (pinfunction "2_2") (pintype "passive"))
      (node (ref "S1") (pin "1") (pinfunction "1_1") (pintype "passive"))
      (node (ref "U5") (pin "10") (pinfunction "PC2_10") (pintype "bidirectional"))
    )
    (net (code "27") (name "/LED_G") (class "Default")
      (node (ref "D2") (pin "K") (pinfunction "K_K") (pintype "passive"))
      (node (ref "U5") (pin "9") (pinfunction "PC1_9") (pintype "bidirectional"))
    )
    (net (code "28") (name "/LED_R") (class "Default")
      (node (ref "D3") (pin "K") (pinfunction "K_K") (pintype "passive"))
      (node (ref "U5") (pin "8") (pinfunction "PC0_8") (pintype "bidirectional"))
    )
    (net (code "29") (name "/NRST") (class "Default")
      (node (ref "C39") (pin "1") (pinfunction "1_1") (pintype "passive"))
      (node (ref "R26") (pin "2") (pinfunction "2_2") (pintype "passive"))
      (node (ref "RESET1") (pin "1") (pinfunction "1_1") (pintype "passive"))
      (node (ref "U5") (pin "7") (pinfunction "NRST_7") (pintype "bidirectional"))
    )
    (net (code "30") (name "/OSC_IN") (class "Default")
      (node (ref "C47") (pin "2") (pinfunction "2_2") (pintype "passive"))
      (node (ref "U5") (pin "5") (pinfunction "PH0-OSC_IN(PH0)_5") (pintype "bidirectional"))
      (node (ref "Y2") (pin "3") (pinfunction "OSC2_3") (pintype "passive"))
    )
    (net (code "31") (name "/OSC_OUT") (class "Default")
      (node (ref "C48") (pin "2") (pinfunction "2_2") (pintype "passive"))
      (node (ref "U5") (pin "6") (pinfunction "PH1-OSC_OUT(PH1)_6") (pintype "bidirectional"))
      (node (ref "Y2") (pin "1") (pinfunction "OSC1_1") (pintype "passive"))
    )
    (net (code "32") (name "/PC12") (class "Default")
      (node (ref "U2") (pin "2") (pinfunction "~{RE}_2") (pintype "input"))
      (node (ref "U2") (pin "3") (pinfunction "DE_3") (pintype "input"))
      (node (ref "U5") (pin "53") (pinfunction "PC12_53") (pintype "bidirectional"))
    )
    (net (code "33") (name "/RDY0") (class "Default")
      (node (ref "*9") (pin "2") (pinfunction "RDY_2") (pintype "passive"))
      (node (ref "R16") (pin "1") (pinfunction "1_1") (pintype "passive"))
      (node (ref "U5") (pin "57") (pinfunction "PB5_57") (pintype "bidirectional"))
    )
    (net (code "34") (name "/RXD") (class "Default")
      (node (ref "U5") (pin "43") (pinfunction "PA10_43") (pintype "bidirectional"))
      (node (ref "U9") (pin "2") (pinfunction "TXD_2") (pintype "passive"))
    )
    (net (code "35") (name "/RXD2") (class "Default")
      (node (ref "U1") (pin "12") (pinfunction "R1OUT_12") (pintype "output"))
      (node (ref "U5") (pin "17") (pinfunction "PA3_17") (pintype "bidirectional"))
    )
    (net (code "36") (name "/RXD2_In") (class "Default")
      (node (ref "RS1") (pin "5") (pinfunction "5_5") (pintype "passive"))
      (node (ref "U1") (pin "13") (pinfunction "R1IN_13") (pintype "input"))
    )
    (net (code "37") (name "/RXD3") (class "Default")
      (node (ref "U2") (pin "1") (pinfunction "RO_1") (pintype "output"))
      (node (ref "U5") (pin "52") (pinfunction "PC11_52") (pintype "bidirectional"))
    )
    (net (code "38") (name "/SCL") (class "Default")
      (node (ref "*10") (pin "6") (pinfunction "SCL_6") (pintype "passive"))
      (node (ref "*9") (pin "10") (pinfunction "SCL_10") (pintype "passive"))
      (node (ref "R17") (pin "1") (pinfunction "1_1") (pintype "passive"))
      (node (ref "U5") (pin "58") (pinfunction "PB6_58") (pintype "bidirectional"))
    )
    (net (code "39") (name "/SDA") (class "Default")
      (node (ref "*10") (pin "1") (pinfunction "SDA_1") (pintype "passive"))
      (node (ref "*9") (pin "9") (pinfunction "SDA_9") (pintype "passive"))
      (node (ref "R21") (pin "1") (pinfunction "1_1") (pintype "passive"))
      (node (ref "U5") (pin "59") (pinfunction "PB7_59") (pintype "bidirectional"))
    )
    (net (code "40") (name "/SWCLK") (class "Default")
      (node (ref "SWD1") (pin "4") (pinfunction "4_4") (pintype "passive"))
      (node (ref "U5") (pin "49") (pinfunction "PA14(JTCK-SWCLK)_49") (pintype "bidirectional"))
    )
    (net (code "41") (name "/SWDIO") (class "Default")
      (node (ref "SWD1") (pin "2") (pinfunction "2_2") (pintype "passive"))
      (node (ref "U5") (pin "46") (pinfunction "PA13(JTMS-SWDIO)_46") (pintype "bidirectional"))
    )
    (net (code "42") (name "/TXD") (class "Default")
      (node (ref "U5") (pin "42") (pinfunction "PA9_42") (pintype "bidirectional"))
      (node (ref "U9") (pin "3") (pinfunction "RXD_3") (pintype "passive"))
    )
    (net (code "43") (name "/TXD2") (class "Default")
      (node (ref "U1") (pin "11") (pinfunction "T1IN_11") (pintype "input"))
      (node (ref "U5") (pin "16") (pinfunction "PA2_16") (pintype "bidirectional"))
    )
    (net (code "44") (name "/TXD2_Out") (class "Default")
      (node (ref "RS1") (pin "3") (pinfunction "3_3") (pintype "passive"))
      (node (ref "U1") (pin "14") (pinfunction "T1OUT_14") (pintype "output"))
    )
    (net (code "45") (name "/TXD3") (class "Default")
      (node (ref "U2") (pin "4") (pinfunction "DI_4") (pintype "input"))
      (node (ref "U5") (pin "51") (pinfunction "PC10_51") (pintype "bidirectional"))
    )
    (net (code "46") (name "/Vout0") (class "Default")
      (node (ref "DA1") (pin "1") (pinfunction "1_1") (pintype "passive"))
      (node (ref "R7") (pin "2") (pinfunction "2_2") (pintype "passive"))
      (node (ref "R9") (pin "1") (pinfunction "1_1") (pintype "passive"))
      (node (ref "U7") (pin "2") (pinfunction "-IN_2") (pintype "input"))
    )
    (net (code "47") (name "/Vout1") (class "Default")
      (node (ref "*3") (pin "15") (pinfunction "Vout_15") (pintype "passive"))
      (node (ref "*3") (pin "16") (pinfunction "Vout_16") (pintype "passive"))
      (node (ref "*3") (pin "6") (pinfunction "-IN_6") (pintype "passive"))
      (node (ref "DA2") (pin "1") (pinfunction "1_1") (pintype "passive"))
    )
    (net (code "48") (name "2.5V") (class "Default")
      (node (ref "*1") (pin "17") (pinfunction "REFIN_17") (pintype "passive"))
      (node (ref "*2") (pin "2") (pinfunction "V+_2") (pintype "passive"))
      (node (ref "C6") (pin "2") (pinfunction "2_2") (pintype "passive"))
      (node (ref "R2") (pin "1") (pinfunction "1_1") (pintype "passive"))
    )
    (net (code "49") (name "3.3V") (class "Default")
      (node (ref "*10") (pin "5") (pinfunction "VDD_5") (pintype "passive"))
      (node (ref "C28") (pin "2") (pinfunction "2_2") (pintype "passive"))
      (node (ref "C29") (pin "2") (pinfunction "2_2") (pintype "passive"))
      (node (ref "C50") (pin "1") (pinfunction "1_1") (pintype "passive"))
      (node (ref "C51") (pin "1") (pinfunction "1_1") (pintype "passive"))
      (node (ref "C52") (pin "1") (pinfunction "1_1") (pintype "passive"))
      (node (ref "C54") (pin "1") (pinfunction "1_1") (pintype "passive"))
      (node (ref "C55") (pin "1") (pinfunction "1_1") (pintype "passive"))
      (node (ref "L4") (pin "2") (pinfunction "2_2") (pintype "passive"))
      (node (ref "R16") (pin "2") (pinfunction "2_2") (pintype "passive"))
      (node (ref "R17") (pin "2") (pinfunction "2_2") (pintype "passive"))
      (node (ref "R21") (pin "2") (pinfunction "2_2") (pintype "passive"))
      (node (ref "R22") (pin "2") (pinfunction "2_2") (pintype "passive"))
      (node (ref "R23") (pin "2") (pinfunction "2_2") (pintype "passive"))
      (node (ref "R25") (pin "2") (pinfunction "2_2") (pintype "passive"))
      (node (ref "R26") (pin "1") (pinfunction "1_1") (pintype "passive"))
      (node (ref "R3") (pin "1") (pinfunction "1_1") (pintype "passive"))
      (node (ref "R4") (pin "1") (pinfunction "1_1") (pintype "passive"))
      (node (ref "R5") (pin "1") (pinfunction "1_1") (pintype "passive"))
      (node (ref "U5") (pin "1") (pinfunction "VBAT_1") (pintype "power_in"))
      (node (ref "U5") (pin "19") (pinfunction "VDD_19") (pintype "power_in"))
      (node (ref "U5") (pin "32") (pinfunction "VDD_32") (pintype "power_in"))
      (node (ref "U5") (pin "48") (pinfunction "VDD_48") (pintype "power_in"))
      (node (ref "U5") (pin "64") (pinfunction "VDD_64") (pintype "power_in"))
      (node (ref "VR1") (pin "2") (pinfunction "Vout_2") (pintype "passive"))
    )
    (net (code "50") (name "GND") (class "Default")
      (node (ref "*1") (pin "15") (pinfunction "GND_15") (pintype "passive"))
      (node (ref "*10") (pin "2") (pinfunction "VSS_2") (pintype "passive"))
      (node (ref "*5") (pin "2") (pinfunction "2_2") (pintype "passive"))
      (node (ref "C1") (pin "1") (pinfunction "1_1") (pintype "passive"))
      (node (ref "C18") (pin "2") (pinfunction "2_2") (pintype "passive"))
      (node (ref "C19") (pin "1") (pinfunction "1_1") (pintype "passive"))
      (node (ref "C20") (pin "2") (pinfunction "2_2") (pintype "passive"))
      (node (ref "C22") (pin "1") (pinfunction "1_1") (pintype "passive"))
      (node (ref "C23") (pin "2") (pinfunction "2_2") (pintype "passive"))
      (node (ref "C26") (pin "1") (pinfunction "1_1") (pintype "passive"))
      (node (ref "C27") (pin "1") (pinfunction "1_1") (pintype "passive"))
      (node (ref "C28") (pin "1") (pinfunction "1_1") (pintype "passive"))
      (node (ref "C29") (pin "1") (pinfunction "1_1") (pintype "passive"))
      (node (ref "C3") (pin "2") (pinfunction "2_2") (pintype "passive"))
      (node (ref "C39") (pin "2") (pinfunction "2_2") (pintype "passive"))
      (node (ref "C40") (pin "2") (pinfunction "2_2") (pintype "passive"))
      (node (ref "C41") (pin "2") (pinfunction "2_2") (pintype "passive"))
      (node (ref "C42") (pin "1") (pinfunction "1_1") (pintype "passive"))
      (node (ref "C43") (pin "2") (pinfunction "2_2") (pintype "passive"))
      (node (ref "C45") (pin "1") (pinfunction "1_1") (pintype "passive"))
      (node (ref "C46") (pin "1") (pinfunction "1_1") (pintype "passive"))
      (node (ref "C47") (pin "1") (pinfunction "1_1") (pintype "passive"))
      (node (ref "C48") (pin "1") (pinfunction "1_1") (pintype "passive"))
      (node (ref "C49") (pin "1") (pinfunction "1_1") (pintype "passive"))
      (node (ref "C5") (pin "2") (pinfunction "2_2") (pintype "passive"))
      (node (ref "C50") (pin "2") (pinfunction "2_2") (pintype "passive"))
      (node (ref "C51") (pin "2") (pinfunction "2_2") (pintype "passive"))
      (node (ref "C52") (pin "2") (pinfunction "2_2") (pintype "passive"))
      (node (ref "C53") (pin "2") (pinfunction "2_2") (pintype "passive"))
      (node (ref "C54") (pin "2") (pinfunction "2_2") (pintype "passive"))
      (node (ref "C55") (pin "2") (pinfunction "2_2") (pintype "passive"))
      (node (ref "C7") (pin "1") (pinfunction "1_1") (pintype "passive"))
      (node (ref "C8") (pin "2") (pinfunction "2_2") (pintype "passive"))
      (node (ref "C9") (pin "2") (pinfunction "2_2") (pintype "passive"))
      (node (ref "D1") (pin "1") (pinfunction "A_1") (pintype "passive"))
      (node (ref "D7") (pin "1") (pinfunction "A_1") (pintype "passive"))
      (node (ref "D8") (pin "2") (pinfunction "K_2") (pintype "passive"))
      (node (ref "D9") (pin "K") (pinfunction "K_K") (pintype "passive"))
      (node (ref "L2") (pin "2") (pinfunction "2_2") (pintype "passive"))
      (node (ref "L3") (pin "1") (pinfunction "1_1") (pintype "passive"))
      (node (ref "R27") (pin "1") (pinfunction "1_1") (pintype "passive"))
      (node (ref "RESET1") (pin "2") (pinfunction "2_2") (pintype "passive"))
      (node (ref "RS1") (pin "4") (pinfunction "4_4") (pintype "passive"))
      (node (ref "RS2") (pin "3") (pinfunction "3_3") (pintype "passive"))
      (node (ref "S1") (pin "2") (pinfunction "2_2") (pintype "passive"))
      (node (ref "SWD1") (pin "3") (pinfunction "3_3") (pintype "passive"))
      (node (ref "U1") (pin "15") (pinfunction "GND_15") (pintype "power_in"))
      (node (ref "U10") (pin "2") (pinfunction "GND_2") (pintype "passive"))
      (node (ref "U10") (pin "8") (pinfunction "S_8") (pintype "passive"))
      (node (ref "U2") (pin "5") (pinfunction "GND_5") (pintype "power_in"))
      (node (ref "U3") (pin "3") (pinfunction "GND_3") (pintype "power_in"))
      (node (ref "U3") (pin "5") (pinfunction "~{ON}/OFF_5") (pintype "input"))
      (node (ref "U3") (pin "6") (pinfunction "6_6") (pintype "power_in"))
      (node (ref "U4") (pin "4") (pinfunction "FB_4") (pintype "input"))
      (node (ref "U5") (pin "12") (pinfunction "VSSA_12") (pintype "power_in"))
      (node (ref "U5") (pin "18") (pinfunction "VSS_18") (pintype "power_in"))
      (node (ref "U5") (pin "63") (pinfunction "VSS_63") (pintype "power_in"))
      (node (ref "U9") (pin "1") (pinfunction "GND_1") (pintype "passive"))
      (node (ref "USB_USART1") (pin "5") (pinfunction "VSS_5") (pintype "passive"))
      (node (ref "VR1") (pin "1") (pinfunction "GND_1") (pintype "passive"))
    )
    (net (code "51") (name "Net-(*3-E{slash}S#)") (class "Default")
      (node (ref "*3") (pin "4") (pinfunction "E/S#_4") (pintype "passive"))
      (node (ref "*3") (pin "7") (pinfunction "Vdig_7") (pintype "passive"))
      (node (ref "D5") (pin "2") (pinfunction "K_2") (pintype "passive"))
      (node (ref "R6") (pin "1") (pinfunction "1_1") (pintype "passive"))
    )
    (net (code "52") (name "Net-(*3-Iset)") (class "Default")
      (node (ref "*3") (pin "9") (pinfunction "Iset_9") (pintype "passive"))
      (node (ref "C24") (pin "2") (pinfunction "2_2") (pintype "passive"))
      (node (ref "R10") (pin "2") (pinfunction "2_2") (pintype "passive"))
    )
    (net (code "53") (name "Net-(*4--IN)") (class "Default")
      (node (ref "*4") (pin "15") (pinfunction "Vout_15") (pintype "passive"))
      (node (ref "*4") (pin "16") (pinfunction "Vout_16") (pintype "passive"))
      (node (ref "*4") (pin "6") (pinfunction "-IN_6") (pintype "passive"))
      (node (ref "R7") (pin "1") (pinfunction "1_1") (pintype "passive"))
      (node (ref "U7") (pin "3") (pinfunction "+IN_3") (pintype "input"))
    )
    (net (code "54") (name "Net-(*4-E{slash}S#)") (class "Default")
      (node (ref "*4") (pin "4") (pinfunction "E/S#_4") (pintype "passive"))
      (node (ref "*4") (pin "7") (pinfunction "Vdig_7") (pintype "passive"))
      (node (ref "D6") (pin "2") (pinfunction "K_2") (pintype "passive"))
      (node (ref "R8") (pin "1") (pinfunction "1_1") (pintype "passive"))
    )
    (net (code "55") (name "Net-(*4-Iset)") (class "Default")
      (node (ref "*4") (pin "9") (pinfunction "Iset_9") (pintype "passive"))
      (node (ref "C25") (pin "2") (pinfunction "2_2") (pintype "passive"))
      (node (ref "R11") (pin "2") (pinfunction "2_2") (pintype "passive"))
    )
    (net (code "56") (name "Net-(*6-V+)") (class "Default")
      (node (ref "*6") (pin "2") (pinfunction "V+_2") (pintype "passive"))
      (node (ref "C30") (pin "2") (pinfunction "2_2") (pintype "passive"))
      (node (ref "R18") (pin "1") (pinfunction "1_1") (pintype "passive"))
      (node (ref "U7") (pin "5") (pinfunction "REF_5") (pintype "input"))
    )
    (net (code "57") (name "Net-(*7-V+)") (class "Default")
      (node (ref "*7") (pin "2") (pinfunction "V+_2") (pintype "passive"))
      (node (ref "C31") (pin "2") (pinfunction "2_2") (pintype "passive"))
      (node (ref "R19") (pin "1") (pinfunction "1_1") (pintype "passive"))
      (node (ref "U8") (pin "5") (pinfunction "REF_5") (pintype "input"))
    )
    (net (code "58") (name "Net-(*8-V+)") (class "Default")
      (node (ref "*8") (pin "2") (pinfunction "V+_2") (pintype "passive"))
      (node (ref "C32") (pin "2") (pinfunction "2_2") (pintype "passive"))
      (node (ref "R20") (pin "1") (pinfunction "1_1") (pintype "passive"))
      (node (ref "U6") (pin "5") (pinfunction "REF_5") (pintype "input"))
    )
    (net (code "59") (name "Net-(D1-K)") (class "Default")
      (node (ref "D1") (pin "2") (pinfunction "K_2") (pintype "passive"))
      (node (ref "L1") (pin "1") (pinfunction "1_1") (pintype "passive"))
      (node (ref "U3") (pin "2") (pinfunction "OUT_2") (pintype "power_in"))
    )
    (net (code "60") (name "Net-(D2-PadA)") (class "Default")
      (node (ref "D2") (pin "A") (pinfunction "A_A") (pintype "passive"))
      (node (ref "R3") (pin "2") (pinfunction "2_2") (pintype "passive"))
    )
    (net (code "61") (name "Net-(D3-PadA)") (class "Default")
      (node (ref "D3") (pin "A") (pinfunction "A_A") (pintype "passive"))
      (node (ref "R4") (pin "2") (pinfunction "2_2") (pintype "passive"))
    )
    (net (code "62") (name "Net-(D4-K)") (class "Default")
      (node (ref "D4") (pin "2") (pinfunction "K_2") (pintype "passive"))
      (node (ref "L2") (pin "1") (pinfunction "1_1") (pintype "passive"))
      (node (ref "U4") (pin "2") (pinfunction "OUT_2") (pintype "power_in"))
    )
    (net (code "63") (name "Net-(D9-PadA)") (class "Default")
      (node (ref "D9") (pin "A") (pinfunction "A_A") (pintype "passive"))
      (node (ref "R24") (pin "2") (pinfunction "2_2") (pintype "passive"))
    )
    (net (code "64") (name "Net-(R13-Pad1)") (class "Default")
      (node (ref "R13") (pin "1") (pinfunction "1_1") (pintype "passive"))
      (node (ref "U8") (pin "1") (pinfunction "RG_1") (pintype "passive"))
    )
    (net (code "65") (name "Net-(R13-Pad2)") (class "Default")
      (node (ref "R13") (pin "2") (pinfunction "2_2") (pintype "passive"))
      (node (ref "U8") (pin "8") (pinfunction "RG_8") (pintype "passive"))
    )
    (net (code "66") (name "Net-(R14-Pad1)") (class "Default")
      (node (ref "R14") (pin "1") (pinfunction "1_1") (pintype "passive"))
      (node (ref "U7") (pin "1") (pinfunction "RG_1") (pintype "passive"))
    )
    (net (code "67") (name "Net-(R14-Pad2)") (class "Default")
      (node (ref "R14") (pin "2") (pinfunction "2_2") (pintype "passive"))
      (node (ref "U7") (pin "8") (pinfunction "RG_8") (pintype "passive"))
    )
    (net (code "68") (name "Net-(R15-Pad1)") (class "Default")
      (node (ref "R15") (pin "1") (pinfunction "1_1") (pintype "passive"))
      (node (ref "U6") (pin "1") (pinfunction "RG_1") (pintype "passive"))
    )
    (net (code "69") (name "Net-(R15-Pad2)") (class "Default")
      (node (ref "R15") (pin "2") (pinfunction "2_2") (pintype "passive"))
      (node (ref "U6") (pin "8") (pinfunction "RG_8") (pintype "passive"))
    )
    (net (code "70") (name "Net-(U1-C1+)") (class "Default")
      (node (ref "C2") (pin "2") (pinfunction "2_2") (pintype "passive"))
      (node (ref "U1") (pin "1") (pinfunction "C1+_1") (pintype "passive"))
    )
    (net (code "71") (name "Net-(U1-C1-)") (class "Default")
      (node (ref "C2") (pin "1") (pinfunction "1_1") (pintype "passive"))
      (node (ref "U1") (pin "3") (pinfunction "C1-_3") (pintype "passive"))
    )
    (net (code "72") (name "Net-(U1-C2+)") (class "Default")
      (node (ref "C4") (pin "1") (pinfunction "1_1") (pintype "passive"))
      (node (ref "U1") (pin "4") (pinfunction "C2+_4") (pintype "passive"))
    )
    (net (code "73") (name "Net-(U1-C2-)") (class "Default")
      (node (ref "C4") (pin "2") (pinfunction "2_2") (pintype "passive"))
      (node (ref "U1") (pin "5") (pinfunction "C2-_5") (pintype "passive"))
    )
    (net (code "74") (name "Net-(U1-V+)") (class "Default")
      (node (ref "C5") (pin "1") (pinfunction "1_1") (pintype "passive"))
      (node (ref "U1") (pin "2") (pinfunction "V+_2") (pintype "power_in"))
    )
    (net (code "75") (name "Net-(U1-V-)") (class "Default")
      (node (ref "C8") (pin "1") (pinfunction "1_1") (pintype "passive"))
      (node (ref "U1") (pin "6") (pinfunction "V-_6") (pintype "power_in"))
    )
    (net (code "76") (name "Net-(U5A-BOOT0)") (class "Default")
      (node (ref "R27") (pin "2") (pinfunction "2_2") (pintype "passive"))
      (node (ref "U5") (pin "60") (pinfunction "BOOT0_60") (pintype "input"))
    )
    (net (code "77") (name "Net-(U5A-VCAP_1)") (class "Default")
      (node (ref "C40") (pin "1") (pinfunction "1_1") (pintype "passive"))
      (node (ref "U5") (pin "31") (pinfunction "VCAP_1_31") (pintype "power_in"))
    )
    (net (code "78") (name "Net-(U5A-VCAP_2)") (class "Default")
      (node (ref "C41") (pin "1") (pinfunction "1_1") (pintype "passive"))
      (node (ref "U5") (pin "47") (pinfunction "VCAP_2_47") (pintype "power_in"))
    )
    (net (code "79") (name "Net-(U5B-VDDA)") (class "Default")
      (node (ref "C53") (pin "1") (pinfunction "1_1") (pintype "passive"))
      (node (ref "L4") (pin "1") (pinfunction "1_1") (pintype "passive"))
      (node (ref "U5") (pin "13") (pinfunction "VDDA_13") (pintype "power_in"))
    )
    (net (code "80") (name "Net-(U8-+IN)") (class "Default")
      (node (ref "R12") (pin "1") (pinfunction "1_1") (pintype "passive"))
      (node (ref "R9") (pin "2") (pinfunction "2_2") (pintype "passive"))
      (node (ref "U8") (pin "3") (pinfunction "+IN_3") (pintype "input"))
    )
    (net (code "81") (name "Net-(U9-V3.3)") (class "Default")
      (node (ref "C43") (pin "1") (pinfunction "1_1") (pintype "passive"))
      (node (ref "U9") (pin "4") (pinfunction "V3.3_4") (pintype "passive"))
    )
    (net (code "82") (name "Net-(U9-XI)") (class "Default")
      (node (ref "C45") (pin "2") (pinfunction "2_2") (pintype "passive"))
      (node (ref "U9") (pin "7") (pinfunction "XI_7") (pintype "passive"))
      (node (ref "Y1") (pin "1") (pinfunction "OSC1_1") (pintype "passive"))
    )
    (net (code "83") (name "Net-(U9-XO)") (class "Default")
      (node (ref "C46") (pin "2") (pinfunction "2_2") (pintype "passive"))
      (node (ref "U9") (pin "8") (pinfunction "XO_8") (pintype "passive"))
      (node (ref "Y1") (pin "3") (pinfunction "OSC2_3") (pintype "passive"))
    )
    (net (code "84") (name "SGND") (class "Default")
      (node (ref "*1") (pin "18") (pinfunction "DAC_GND_18") (pintype "passive"))
      (node (ref "*1") (pin "19") (pinfunction "DAC_GND_19") (pintype "passive"))
      (node (ref "*1") (pin "20") (pinfunction "SIG_GND_20") (pintype "passive"))
      (node (ref "*1") (pin "21") (pinfunction "SIG_GND_21") (pintype "passive"))
      (node (ref "*2") (pin "1") (pinfunction "V-_1") (pintype "passive"))
      (node (ref "*6") (pin "1") (pinfunction "V-_1") (pintype "passive"))
      (node (ref "*7") (pin "1") (pinfunction "V-_1") (pintype "passive"))
      (node (ref "*8") (pin "1") (pinfunction "V-_1") (pintype "passive"))
      (node (ref "*9") (pin "1") (pinfunction "ADDR_1") (pintype "passive"))
      (node (ref "*9") (pin "3") (pinfunction "GND_3") (pintype "passive"))
      (node (ref "*9") (pin "7") (pinfunction "AIN3_7") (pintype "passive"))
      (node (ref "C10") (pin "2") (pinfunction "2_2") (pintype "passive"))
      (node (ref "C11") (pin "1") (pinfunction "1_1") (pintype "passive"))
      (node (ref "C12") (pin "1") (pinfunction "1_1") (pintype "passive"))
      (node (ref "C13") (pin "1") (pinfunction "1_1") (pintype "passive"))
      (node (ref "C14") (pin "2") (pinfunction "2_2") (pintype "passive"))
      (node (ref "C15") (pin "1") (pinfunction "1_1") (pintype "passive"))
      (node (ref "C16") (pin "1") (pinfunction "1_1") (pintype "passive"))
      (node (ref "C17") (pin "1") (pinfunction "1_1") (pintype "passive"))
      (node (ref "C30") (pin "1") (pinfunction "1_1") (pintype "passive"))
      (node (ref "C31") (pin "1") (pinfunction "1_1") (pintype "passive"))
      (node (ref "C32") (pin "1") (pinfunction "1_1") (pintype "passive"))
      (node (ref "C33") (pin "1") (pinfunction "1_1") (pintype "passive"))
      (node (ref "C34") (pin "1") (pinfunction "1_1") (pintype "passive"))
      (node (ref "C35") (pin "1") (pinfunction "1_1") (pintype "passive"))
      (node (ref "C36") (pin "1") (pinfunction "1_1") (pintype "passive"))
      (node (ref "C37") (pin "1") (pinfunction "1_1") (pintype "passive"))
      (node (ref "C38") (pin "1") (pinfunction "1_1") (pintype "passive"))
      (node (ref "C44") (pin "2") (pinfunction "2_2") (pintype "passive"))
      (node (ref "C6") (pin "1") (pinfunction "1_1") (pintype "passive"))
      (node (ref "DA1") (pin "2") (pinfunction "2_2") (pintype "passive"))
      (node (ref "DA2") (pin "2") (pinfunction "2_2") (pintype "passive"))
      (node (ref "Force Sensor1") (pin "4") (pinfunction "4_4") (pintype "passive"))
      (node (ref "L3") (pin "2") (pinfunction "2_2") (pintype "passive"))
      (node (ref "R12") (pin "2") (pinfunction "2_2") (pintype "passive"))
      (node (ref "U8") (pin "2") (pinfunction "-IN_2") (pintype "input"))
    )
    (net (code "85") (name "unconnected-(*1-NC-Pad2)") (class "Default")
      (node (ref "*1") (pin "2") (pinfunction "NC_2") (pintype "passive"))
    )
    (net (code "86") (name "unconnected-(*1-NC-Pad4)") (class "Default")
      (node (ref "*1") (pin "4") (pinfunction "NC_4") (pintype "passive"))
    )
    (net (code "87") (name "unconnected-(*1-NC-Pad6)") (class "Default")
      (node (ref "*1") (pin "6") (pinfunction "NC_6") (pintype "passive"))
    )
    (net (code "88") (name "unconnected-(*1-NC-Pad12)") (class "Default")
      (node (ref "*1") (pin "12") (pinfunction "NC_12") (pintype "passive"))
    )
    (net (code "89") (name "unconnected-(*1-NC-Pad13)") (class "Default")
      (node (ref "*1") (pin "13") (pinfunction "NC_13") (pintype "passive"))
    )
    (net (code "90") (name "unconnected-(*1-NC-Pad22)") (class "Default")
      (node (ref "*1") (pin "22") (pinfunction "NC_22") (pintype "passive"))
    )
    (net (code "91") (name "unconnected-(*2-ADJ-Pad3)") (class "Default")
      (node (ref "*2") (pin "3") (pinfunction "ADJ_3") (pintype "passive"))
    )
    (net (code "92") (name "unconnected-(*3-Iflag-Pad8)") (class "Default")
      (node (ref "*3") (pin "8") (pinfunction "Iflag_8") (pintype "passive"))
    )
    (net (code "93") (name "unconnected-(*3-Tflag-Pad3)") (class "Default")
      (node (ref "*3") (pin "3") (pinfunction "Tflag_3") (pintype "passive"))
    )
    (net (code "94") (name "unconnected-(*3-Tsense-Pad12)") (class "Default")
      (node (ref "*3") (pin "12") (pinfunction "Tsense_12") (pintype "passive"))
    )
    (net (code "95") (name "unconnected-(*4-Iflag-Pad8)") (class "Default")
      (node (ref "*4") (pin "8") (pinfunction "Iflag_8") (pintype "passive"))
    )
    (net (code "96") (name "unconnected-(*4-Tflag-Pad3)") (class "Default")
      (node (ref "*4") (pin "3") (pinfunction "Tflag_3") (pintype "passive"))
    )
    (net (code "97") (name "unconnected-(*4-Tsense-Pad12)") (class "Default")
      (node (ref "*4") (pin "12") (pinfunction "Tsense_12") (pintype "passive"))
    )
    (net (code "98") (name "unconnected-(*6-ADJ-Pad3)") (class "Default")
      (node (ref "*6") (pin "3") (pinfunction "ADJ_3") (pintype "passive"))
    )
    (net (code "99") (name "unconnected-(*7-ADJ-Pad3)") (class "Default")
      (node (ref "*7") (pin "3") (pinfunction "ADJ_3") (pintype "passive"))
    )
    (net (code "100") (name "unconnected-(*8-ADJ-Pad3)") (class "Default")
      (node (ref "*8") (pin "3") (pinfunction "ADJ_3") (pintype "passive"))
    )
    (net (code "101") (name "unconnected-(*10-NC-Pad3)") (class "Default")
      (node (ref "*10") (pin "3") (pinfunction "NC_3") (pintype "passive"))
    )
    (net (code "102") (name "unconnected-(*10-NC-Pad4)") (class "Default")
      (node (ref "*10") (pin "4") (pinfunction "NC_4") (pintype "passive"))
    )
    (net (code "103") (name "unconnected-(RS1-Pad1)") (class "Default")
      (node (ref "RS1") (pin "1") (pinfunction "1_1") (pintype "passive"))
    )
    (net (code "104") (name "unconnected-(RS1-Pad2)") (class "Default")
      (node (ref "RS1") (pin "2") (pinfunction "2_2") (pintype "passive"))
    )
    (net (code "105") (name "unconnected-(RS1-Pad6)") (class "Default")
      (node (ref "RS1") (pin "6") (pinfunction "6_6") (pintype "passive"))
    )
    (net (code "106") (name "unconnected-(T1-Pad1)") (class "Default")
      (node (ref "T1") (pin "1") (pinfunction "1_1") (pintype "passive"))
    )
    (net (code "107") (name "unconnected-(T2-Pad1)") (class "Default")
      (node (ref "T2") (pin "1") (pinfunction "1_1") (pintype "passive"))
    )
    (net (code "108") (name "unconnected-(T3-Pad1)") (class "Default")
      (node (ref "T3") (pin "1") (pinfunction "1_1") (pintype "passive"))
    )
    (net (code "109") (name "unconnected-(T4-Pad1)") (class "Default")
      (node (ref "T4") (pin "1") (pinfunction "1_1") (pintype "passive"))
    )
    (net (code "110") (name "unconnected-(U1-R2IN-Pad8)") (class "Default")
      (node (ref "U1") (pin "8") (pinfunction "R2IN_8") (pintype "input+no_connect"))
    )
    (net (code "111") (name "unconnected-(U1-R2OUT-Pad9)") (class "Default")
      (node (ref "U1") (pin "9") (pinfunction "R2OUT_9") (pintype "output"))
    )
    (net (code "112") (name "unconnected-(U1-T2IN-Pad10)") (class "Default")
      (node (ref "U1") (pin "10") (pinfunction "T2IN_10") (pintype "input+no_connect"))
    )
    (net (code "113") (name "unconnected-(U1-T2OUT-Pad7)") (class "Default")
      (node (ref "U1") (pin "7") (pinfunction "T2OUT_7") (pintype "output"))
    )
    (net (code "114") (name "unconnected-(U5A-PA0-WKUP(PA0)-Pad14)") (class "Default")
      (node (ref "U5") (pin "14") (pinfunction "PA0-WKUP(PA0)_14") (pintype "bidirectional"))
    )
    (net (code "115") (name "unconnected-(U5A-PA1-Pad15)") (class "Default")
      (node (ref "U5") (pin "15") (pinfunction "PA1_15") (pintype "bidirectional"))
    )
    (net (code "116") (name "unconnected-(U5A-PA4-Pad20)") (class "Default")
      (node (ref "U5") (pin "20") (pinfunction "PA4_20") (pintype "bidirectional"))
    )
    (net (code "117") (name "unconnected-(U5A-PA5-Pad21)") (class "Default")
      (node (ref "U5") (pin "21") (pinfunction "PA5_21") (pintype "bidirectional"))
    )
    (net (code "118") (name "unconnected-(U5A-PA6-Pad22)") (class "Default")
      (node (ref "U5") (pin "22") (pinfunction "PA6_22") (pintype "bidirectional"))
    )
    (net (code "119") (name "unconnected-(U5A-PA7-Pad23)") (class "Default")
      (node (ref "U5") (pin "23") (pinfunction "PA7_23") (pintype "bidirectional"))
    )
    (net (code "120") (name "unconnected-(U5A-PA8-Pad41)") (class "Default")
      (node (ref "U5") (pin "41") (pinfunction "PA8_41") (pintype "bidirectional"))
    )
    (net (code "121") (name "unconnected-(U5A-PA15(JTDI)-Pad50)") (class "Default")
      (node (ref "U5") (pin "50") (pinfunction "PA15(JTDI)_50") (pintype "bidirectional"))
    )
    (net (code "122") (name "unconnected-(U5A-PB0-Pad26)") (class "Default")
      (node (ref "U5") (pin "26") (pinfunction "PB0_26") (pintype "bidirectional"))
    )
    (net (code "123") (name "unconnected-(U5A-PB1-Pad27)") (class "Default")
      (node (ref "U5") (pin "27") (pinfunction "PB1_27") (pintype "bidirectional"))
    )
    (net (code "124") (name "unconnected-(U5A-PB2-BOOT1(PB2)-Pad28)") (class "Default")
      (node (ref "U5") (pin "28") (pinfunction "PB2-BOOT1(PB2)_28") (pintype "bidirectional"))
    )
    (net (code "125") (name "unconnected-(U5A-PB3(JTDO{slash}TRACESWO)-Pad55)") (class "Default")
      (node (ref "U5") (pin "55") (pinfunction "PB3(JTDO/TRACESWO)_55") (pintype "bidirectional"))
    )
    (net (code "126") (name "unconnected-(U5A-PB4(NJTRST)-Pad56)") (class "Default")
      (node (ref "U5") (pin "56") (pinfunction "PB4(NJTRST)_56") (pintype "bidirectional"))
    )
    (net (code "127") (name "unconnected-(U5A-PB8-Pad61)") (class "Default")
      (node (ref "U5") (pin "61") (pinfunction "PB8_61") (pintype "bidirectional"))
    )
    (net (code "128") (name "unconnected-(U5A-PB9-Pad62)") (class "Default")
      (node (ref "U5") (pin "62") (pinfunction "PB9_62") (pintype "bidirectional"))
    )
    (net (code "129") (name "unconnected-(U5A-PC3-Pad11)") (class "Default")
      (node (ref "U5") (pin "11") (pinfunction "PC3_11") (pintype "bidirectional"))
    )
    (net (code "130") (name "unconnected-(U5A-PC4-Pad24)") (class "Default")
      (node (ref "U5") (pin "24") (pinfunction "PC4_24") (pintype "bidirectional"))
    )
    (net (code "131") (name "unconnected-(U5A-PC5-Pad25)") (class "Default")
      (node (ref "U5") (pin "25") (pinfunction "PC5_25") (pintype "bidirectional"))
    )
    (net (code "132") (name "unconnected-(U5A-PC6-Pad37)") (class "Default")
      (node (ref "U5") (pin "37") (pinfunction "PC6_37") (pintype "bidirectional"))
    )
    (net (code "133") (name "unconnected-(U5A-PC7-Pad38)") (class "Default")
      (node (ref "U5") (pin "38") (pinfunction "PC7_38") (pintype "bidirectional"))
    )
    (net (code "134") (name "unconnected-(U5A-PC8-Pad39)") (class "Default")
      (node (ref "U5") (pin "39") (pinfunction "PC8_39") (pintype "bidirectional"))
    )
    (net (code "135") (name "unconnected-(U5A-PC9-Pad40)") (class "Default")
      (node (ref "U5") (pin "40") (pinfunction "PC9_40") (pintype "bidirectional"))
    )
    (net (code "136") (name "unconnected-(U5A-PC13-Pad2)") (class "Default")
      (node (ref "U5") (pin "2") (pinfunction "PC13_2") (pintype "bidirectional"))
    )
    (net (code "137") (name "unconnected-(U5A-PC14-OSC32_IN(PC14)-Pad3)") (class "Default")
      (node (ref "U5") (pin "3") (pinfunction "PC14-OSC32_IN(PC14)_3") (pintype "bidirectional"))
    )
    (net (code "138") (name "unconnected-(U5A-PC15-OSC32_OUT(PC15)-Pad4)") (class "Default")
      (node (ref "U5") (pin "4") (pinfunction "PC15-OSC32_OUT(PC15)_4") (pintype "bidirectional"))
    )
    (net (code "139") (name "unconnected-(U5A-PD2-Pad54)") (class "Default")
      (node (ref "U5") (pin "54") (pinfunction "PD2_54") (pintype "bidirectional"))
    )
    (net (code "140") (name "unconnected-(U9-CTS#-Pad9)") (class "Default")
      (node (ref "U9") (pin "9") (pinfunction "CTS#_9") (pintype "passive"))
    )
    (net (code "141") (name "unconnected-(U9-DCD#-Pad13)") (class "Default")
      (node (ref "U9") (pin "13") (pinfunction "DCD#_13") (pintype "passive"))
    )
    (net (code "142") (name "unconnected-(U9-DSR#-Pad10)") (class "Default")
      (node (ref "U9") (pin "10") (pinfunction "DSR#_10") (pintype "passive"))
    )
    (net (code "143") (name "unconnected-(U9-DTR#-Pad12)") (class "Default")
      (node (ref "U9") (pin "12") (pinfunction "DTR#_12") (pintype "passive"))
    )
    (net (code "144") (name "unconnected-(U9-R232-Pad15)") (class "Default")
      (node (ref "U9") (pin "15") (pinfunction "R232_15") (pintype "passive"))
    )
    (net (code "145") (name "unconnected-(U9-RI#-Pad14)") (class "Default")
      (node (ref "U9") (pin "14") (pinfunction "RI#_14") (pintype "passive"))
    )
    (net (code "146") (name "unconnected-(U9-RTS#-Pad11)") (class "Default")
      (node (ref "U9") (pin "11") (pinfunction "RTS#_11") (pintype "passive"))
    )
    (net (code "147") (name "unconnected-(U10-n.c.-Pad5)") (class "Default")
      (node (ref "U10") (pin "5") (pinfunction "n.c._5") (pintype "passive"))
    )
    (net (code "148") (name "unconnected-(USB_USART1-ID-Pad4)") (class "Default")
      (node (ref "USB_USART1") (pin "4") (pinfunction "ID_4") (pintype "passive"))
    )
  )
)
